# powerSupplyBoard_new.net
KiCad netlist of a schematic drawn in EAGLE
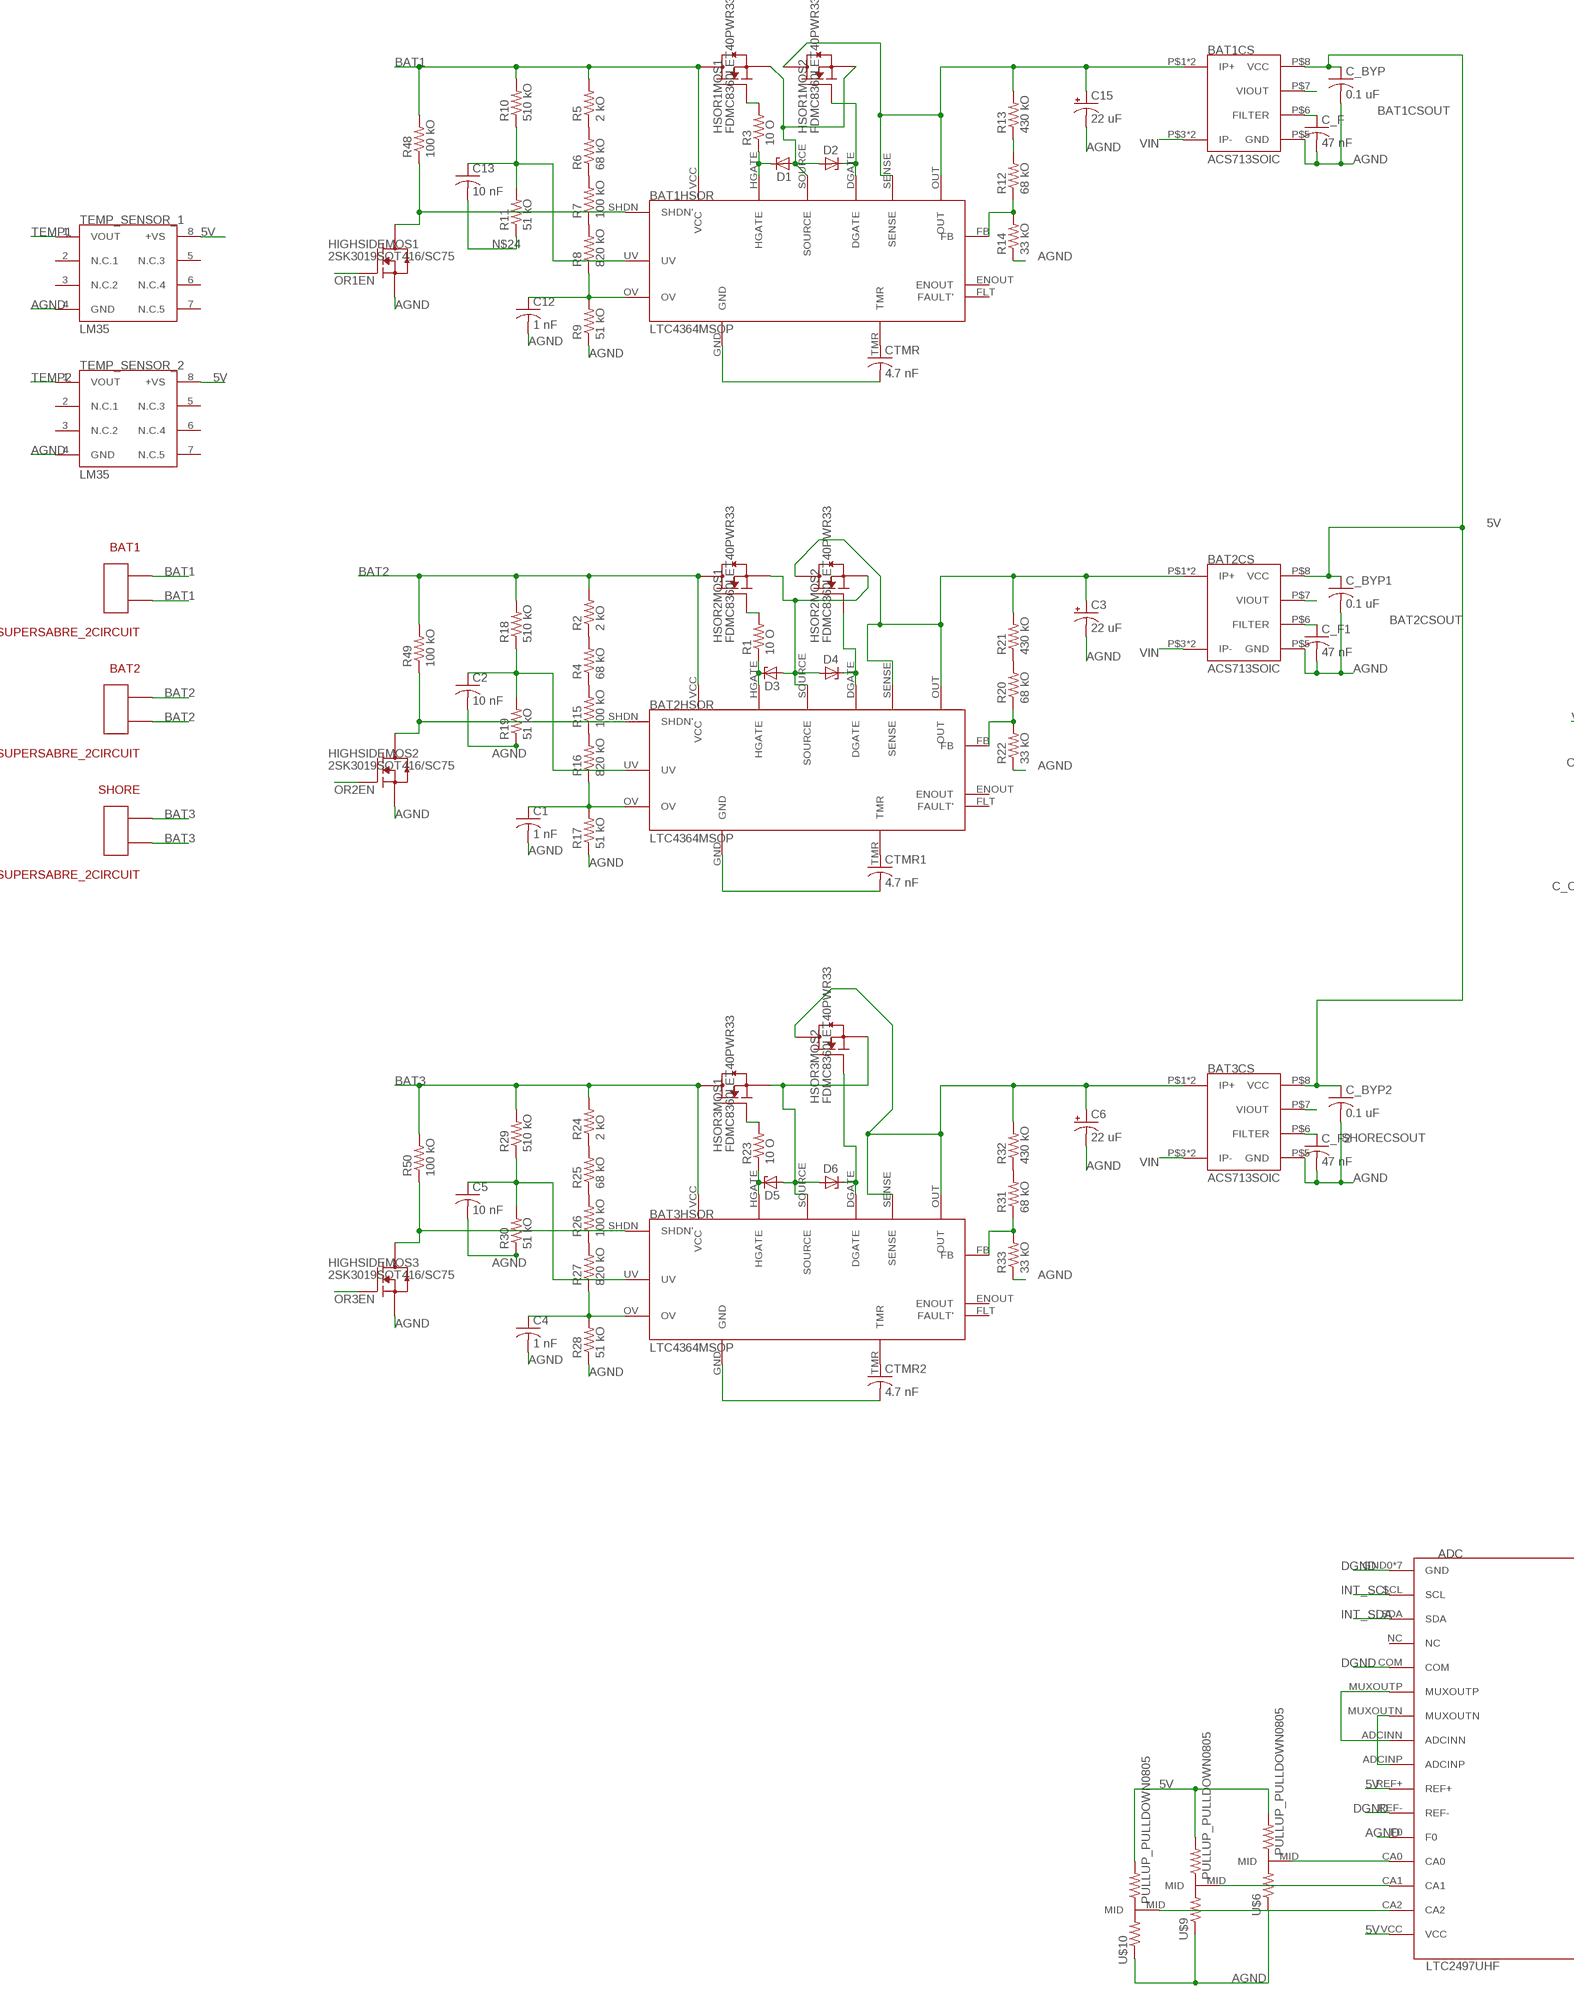
[diagram p0: schematic, sheet 1, part 1 of 2]
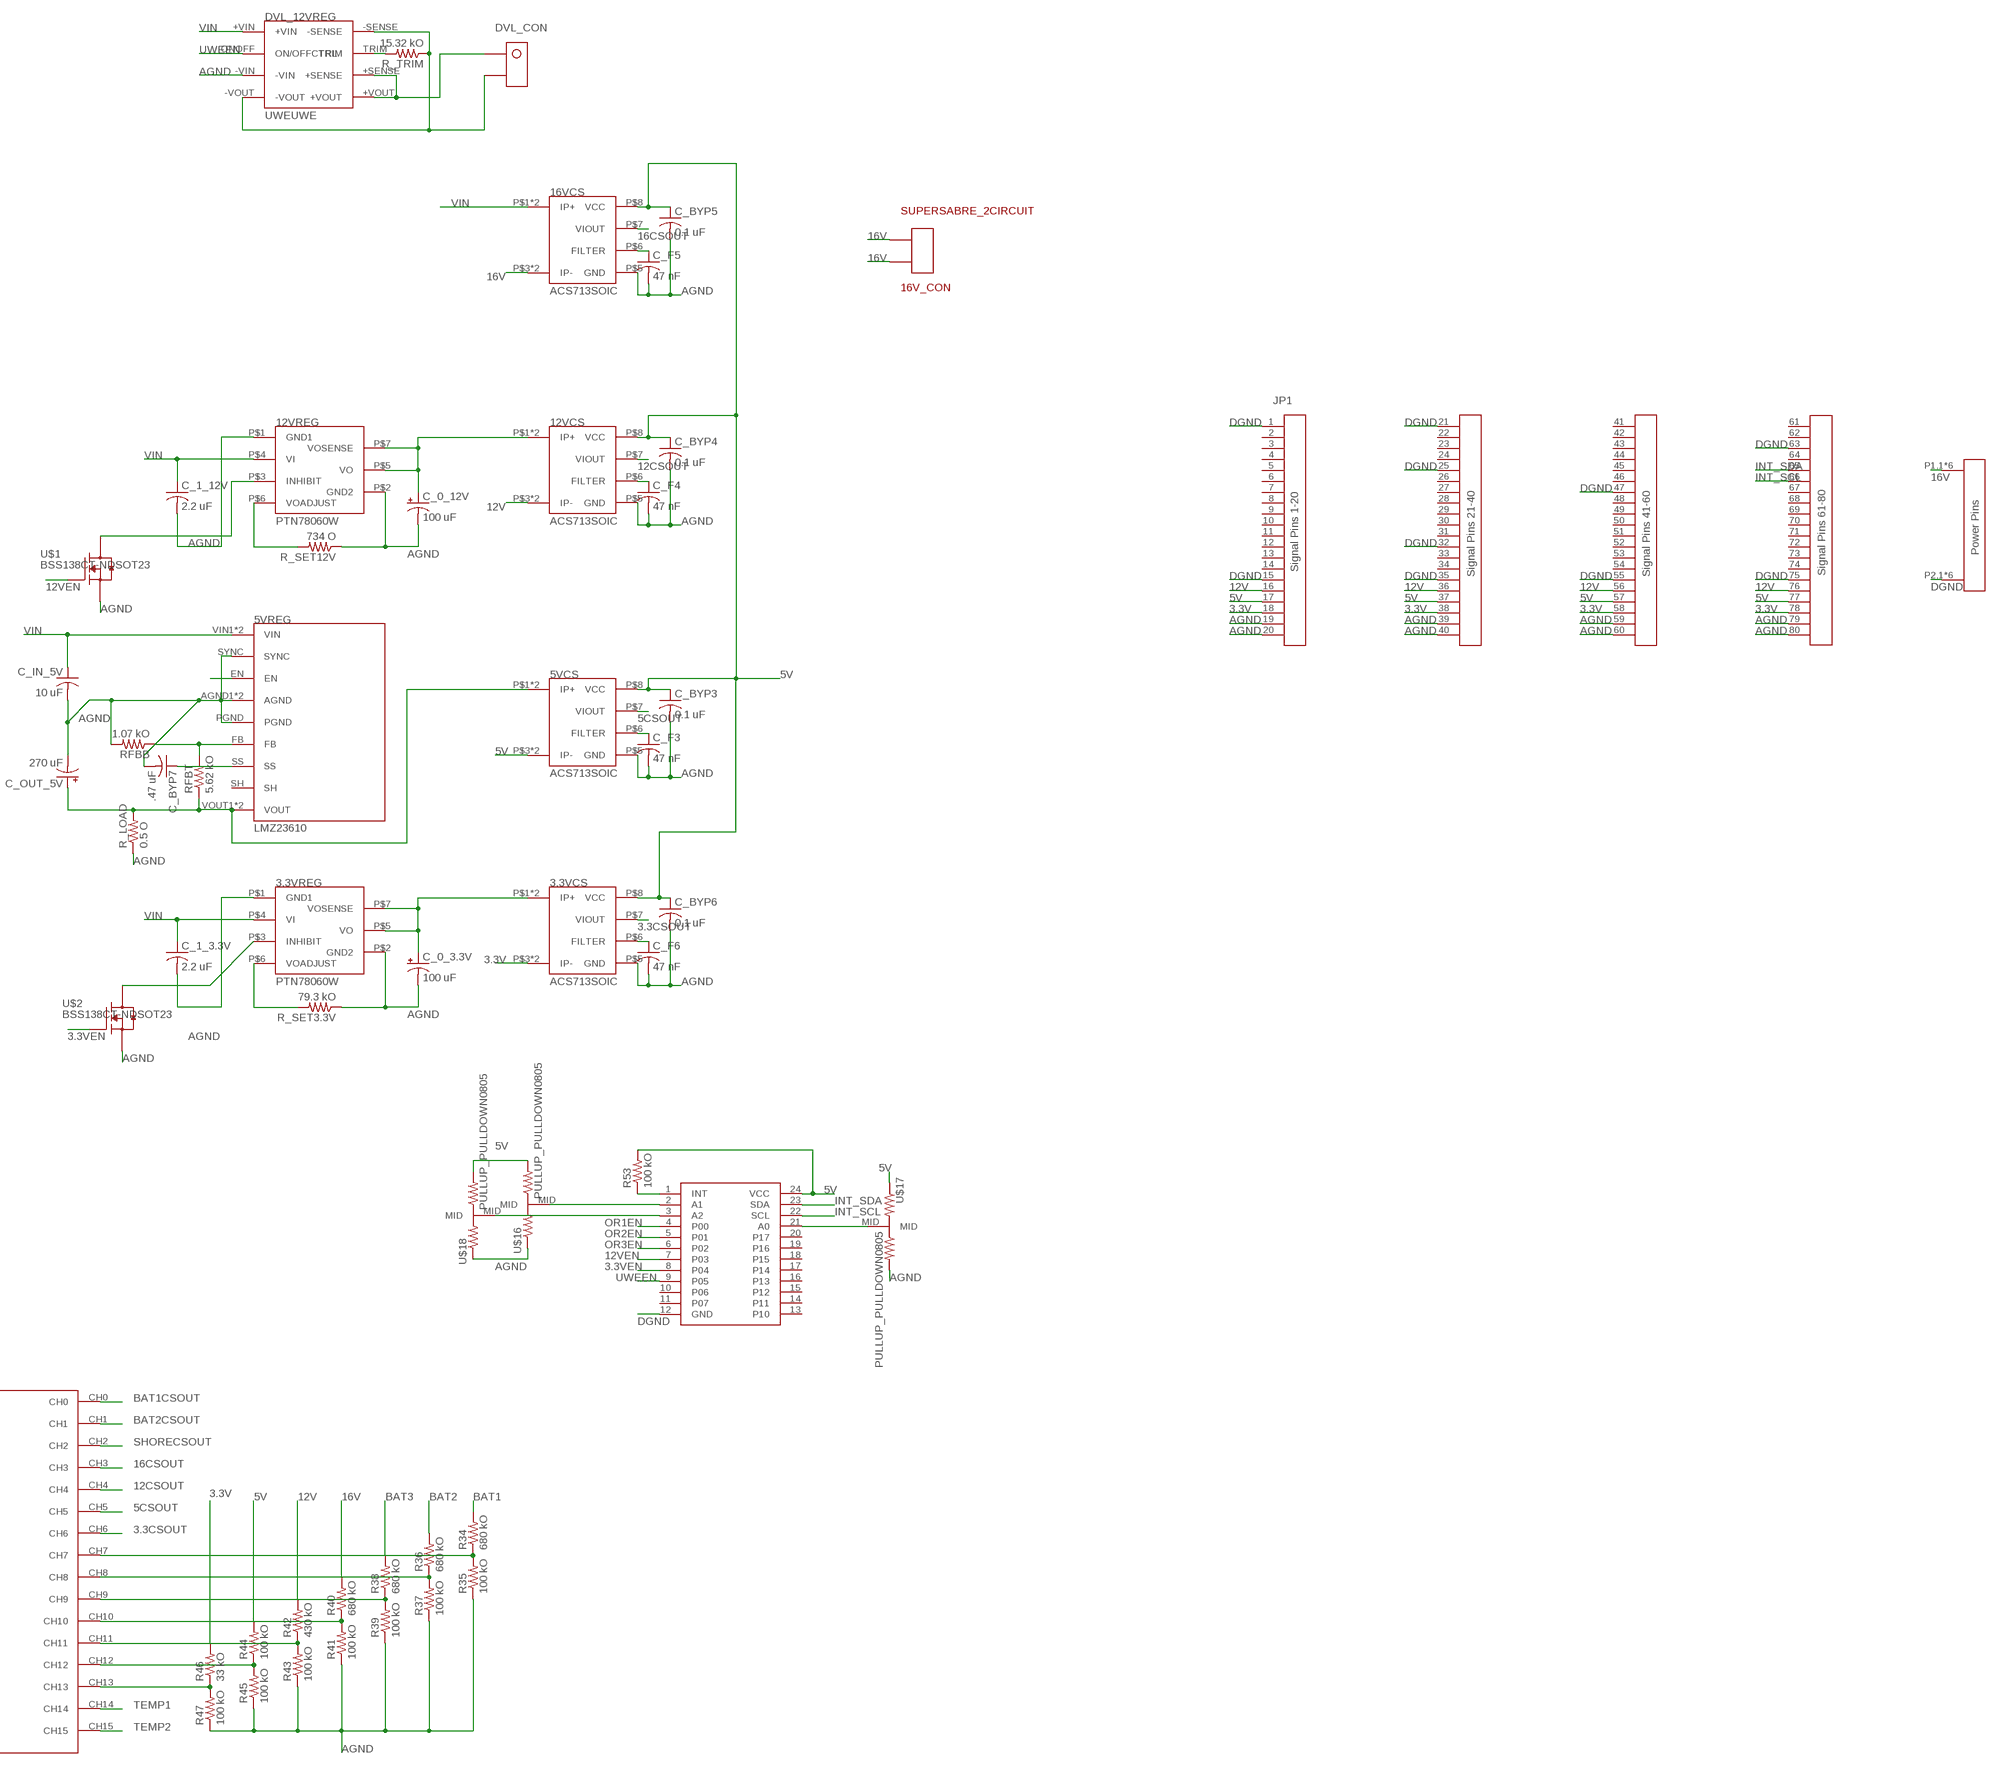
[diagram p1: schematic, sheet 1, part 2 of 2]

(export (version "E")
  (design (tool "Eeschema 10.0.6"))
  (components
    (comp (ref "3.3VCS")
      (value "ACS713SOIC")
      (footprint "eagle-import:ACS713-SOIC")
      (libsource (lib "eagle-import") (part "ACS713SOIC"))
    )
    (comp (ref "3.3VREG")
      (value "PTN78060W")
      (footprint "eagle-import:PTN78060W")
      (libsource (lib "eagle-import") (part "PTN78060W"))
    )
    (comp (ref "5VCS")
      (value "ACS713SOIC")
      (footprint "eagle-import:ACS713-SOIC")
      (libsource (lib "eagle-import") (part "ACS713SOIC"))
    )
    (comp (ref "5VREG")
      (value "LMZ23610")
      (footprint "eagle-import:LMZ23610")
      (libsource (lib "eagle-import") (part "LMZ23610"))
    )
    (comp (ref "12VCS")
      (value "ACS713SOIC")
      (footprint "eagle-import:ACS713-SOIC")
      (libsource (lib "eagle-import") (part "ACS713SOIC"))
    )
    (comp (ref "12VREG")
      (value "PTN78060W")
      (footprint "eagle-import:PTN78060W")
      (libsource (lib "eagle-import") (part "PTN78060W"))
    )
    (comp (ref "16VCS")
      (value "ACS713SOIC")
      (footprint "eagle-import:ACS713-SOIC")
      (libsource (lib "eagle-import") (part "ACS713SOIC"))
    )
    (comp (ref "16V_CON")
      (value "SUPERSABRE_2CIRCUIT")
      (footprint "eagle-import:SUPERSABRE_2CIRCUIT")
      (libsource (lib "eagle-import") (part "SUPERSABRE_2CIRCUIT"))
    )
    (comp (ref "ADC")
      (value "LTC2497UHF")
      (footprint "eagle-import:LTC2497-UHF")
      (libsource (lib "eagle-import") (part "LTC2497UHF"))
    )
    (comp (ref "BAT1")
      (value "SUPERSABRE_2CIRCUIT")
      (footprint "eagle-import:SUPERSABRE_2CIRCUIT")
      (libsource (lib "eagle-import") (part "SUPERSABRE_2CIRCUIT"))
    )
    (comp (ref "BAT1CS")
      (value "ACS713SOIC")
      (footprint "eagle-import:ACS713-SOIC")
      (libsource (lib "eagle-import") (part "ACS713SOIC"))
    )
    (comp (ref "BAT1HSOR")
      (value "LTC4364MSOP")
      (footprint "eagle-import:MSOP16")
      (libsource (lib "eagle-import") (part "LTC4364MSOP"))
    )
    (comp (ref "BAT2")
      (value "SUPERSABRE_2CIRCUIT")
      (footprint "eagle-import:SUPERSABRE_2CIRCUIT")
      (libsource (lib "eagle-import") (part "SUPERSABRE_2CIRCUIT"))
    )
    (comp (ref "BAT2CS")
      (value "ACS713SOIC")
      (footprint "eagle-import:ACS713-SOIC")
      (libsource (lib "eagle-import") (part "ACS713SOIC"))
    )
    (comp (ref "BAT2HSOR")
      (value "LTC4364MSOP")
      (footprint "eagle-import:MSOP16")
      (libsource (lib "eagle-import") (part "LTC4364MSOP"))
    )
    (comp (ref "BAT3CS")
      (value "ACS713SOIC")
      (footprint "eagle-import:ACS713-SOIC")
      (libsource (lib "eagle-import") (part "ACS713SOIC"))
    )
    (comp (ref "BAT3HSOR")
      (value "LTC4364MSOP")
      (footprint "eagle-import:MSOP16")
      (libsource (lib "eagle-import") (part "LTC4364MSOP"))
    )
    (comp (ref "C1")
      (value "1 nF")
      (footprint "eagle-import:C0805")
      (libsource (lib "eagle-import") (part "C-USC0805"))
    )
    (comp (ref "C2")
      (value "10 nF")
      (footprint "eagle-import:C0805")
      (libsource (lib "eagle-import") (part "C-USC0805"))
    )
    (comp (ref "C3")
      (value "22 uF")
      (footprint "eagle-import:PANASONIC_F")
      (libsource (lib "eagle-import") (part "CPOL-USF"))
    )
    (comp (ref "C4")
      (value "1 nF")
      (footprint "eagle-import:C0805")
      (libsource (lib "eagle-import") (part "C-USC0805"))
    )
    (comp (ref "C5")
      (value "10 nF")
      (footprint "eagle-import:C0805")
      (libsource (lib "eagle-import") (part "C-USC0805"))
    )
    (comp (ref "C6")
      (value "22 uF")
      (footprint "eagle-import:PANASONIC_F")
      (libsource (lib "eagle-import") (part "CPOL-USF"))
    )
    (comp (ref "C12")
      (value "1 nF")
      (footprint "eagle-import:C0805")
      (libsource (lib "eagle-import") (part "C-USC0805"))
    )
    (comp (ref "C13")
      (value "10 nF")
      (footprint "eagle-import:C0805")
      (libsource (lib "eagle-import") (part "C-USC0805"))
    )
    (comp (ref "C15")
      (value "22 uF")
      (footprint "eagle-import:PANASONIC_F")
      (libsource (lib "eagle-import") (part "CPOL-USF"))
    )
    (comp (ref "CTMR")
      (value "4.7 nF")
      (footprint "eagle-import:C0805")
      (libsource (lib "eagle-import") (part "C-USC0805"))
    )
    (comp (ref "CTMR1")
      (value "4.7 nF")
      (footprint "eagle-import:C0805")
      (libsource (lib "eagle-import") (part "C-USC0805"))
    )
    (comp (ref "CTMR2")
      (value "4.7 nF")
      (footprint "eagle-import:C0805")
      (libsource (lib "eagle-import") (part "C-USC0805"))
    )
    (comp (ref "C_0_3.3V")
      (value "100 uF")
      (footprint "eagle-import:PANASONIC_F")
      (libsource (lib "eagle-import") (part "CPOL-USF"))
    )
    (comp (ref "C_0_12V")
      (value "100 uF")
      (footprint "eagle-import:PANASONIC_F")
      (libsource (lib "eagle-import") (part "CPOL-USF"))
    )
    (comp (ref "C_1_3.3V")
      (value "2.2 uF")
      (footprint "eagle-import:C0805")
      (libsource (lib "eagle-import") (part "C-USC0805"))
    )
    (comp (ref "C_1_12V")
      (value "2.2 uF")
      (footprint "eagle-import:C0805")
      (libsource (lib "eagle-import") (part "C-USC0805"))
    )
    (comp (ref "C_BYP")
      (value "0.1 uF")
      (footprint "eagle-import:C0805")
      (libsource (lib "eagle-import") (part "C-USC0805"))
    )
    (comp (ref "C_BYP1")
      (value "0.1 uF")
      (footprint "eagle-import:C0805")
      (libsource (lib "eagle-import") (part "C-USC0805"))
    )
    (comp (ref "C_BYP2")
      (value "0.1 uF")
      (footprint "eagle-import:C0805")
      (libsource (lib "eagle-import") (part "C-USC0805"))
    )
    (comp (ref "C_BYP3")
      (value "0.1 uF")
      (footprint "eagle-import:C0805")
      (libsource (lib "eagle-import") (part "C-USC0805"))
    )
    (comp (ref "C_BYP4")
      (value "0.1 uF")
      (footprint "eagle-import:C0805")
      (libsource (lib "eagle-import") (part "C-USC0805"))
    )
    (comp (ref "C_BYP5")
      (value "0.1 uF")
      (footprint "eagle-import:C0805")
      (libsource (lib "eagle-import") (part "C-USC0805"))
    )
    (comp (ref "C_BYP6")
      (value "0.1 uF")
      (footprint "eagle-import:C0805")
      (libsource (lib "eagle-import") (part "C-USC0805"))
    )
    (comp (ref "C_BYP7")
      (value ".47 uF")
      (footprint "eagle-import:C0805")
      (libsource (lib "eagle-import") (part "C-USC0805"))
    )
    (comp (ref "C_F")
      (value "47 nF")
      (footprint "eagle-import:C0805")
      (libsource (lib "eagle-import") (part "C-USC0805"))
    )
    (comp (ref "C_F1")
      (value "47 nF")
      (footprint "eagle-import:C0805")
      (libsource (lib "eagle-import") (part "C-USC0805"))
    )
    (comp (ref "C_F2")
      (value "47 nF")
      (footprint "eagle-import:C0805")
      (libsource (lib "eagle-import") (part "C-USC0805"))
    )
    (comp (ref "C_F3")
      (value "47 nF")
      (footprint "eagle-import:C0805")
      (libsource (lib "eagle-import") (part "C-USC0805"))
    )
    (comp (ref "C_F4")
      (value "47 nF")
      (footprint "eagle-import:C0805")
      (libsource (lib "eagle-import") (part "C-USC0805"))
    )
    (comp (ref "C_F5")
      (value "47 nF")
      (footprint "eagle-import:C0805")
      (libsource (lib "eagle-import") (part "C-USC0805"))
    )
    (comp (ref "C_F6")
      (value "47 nF")
      (footprint "eagle-import:C0805")
      (libsource (lib "eagle-import") (part "C-USC0805"))
    )
    (comp (ref "C_IN_5V")
      (value "10 uF")
      (footprint "eagle-import:C0805")
      (libsource (lib "eagle-import") (part "C-USC0805"))
    )
    (comp (ref "C_OUT_5V")
      (value "270 uF")
      (footprint "eagle-import:PANASONIC_F")
      (libsource (lib "eagle-import") (part "CPOL-USF"))
    )
    (comp (ref "D1")
      (value "ZENER-DIODESOD323-W")
      (footprint "eagle-import:SOD323-W")
      (libsource (lib "eagle-import") (part "ZENER-DIODESOD323-W"))
    )
    (comp (ref "D2")
      (value "ZENER-DIODESOD323-W")
      (footprint "eagle-import:SOD323-W")
      (libsource (lib "eagle-import") (part "ZENER-DIODESOD323-W"))
    )
    (comp (ref "D3")
      (value "ZENER-DIODESOD323-W")
      (footprint "eagle-import:SOD323-W")
      (libsource (lib "eagle-import") (part "ZENER-DIODESOD323-W"))
    )
    (comp (ref "D4")
      (value "ZENER-DIODESOD323-W")
      (footprint "eagle-import:SOD323-W")
      (libsource (lib "eagle-import") (part "ZENER-DIODESOD323-W"))
    )
    (comp (ref "D5")
      (value "ZENER-DIODESOD323-W")
      (footprint "eagle-import:SOD323-W")
      (libsource (lib "eagle-import") (part "ZENER-DIODESOD323-W"))
    )
    (comp (ref "D6")
      (value "ZENER-DIODESOD323-W")
      (footprint "eagle-import:SOD323-W")
      (libsource (lib "eagle-import") (part "ZENER-DIODESOD323-W"))
    )
    (comp (ref "DVL_12VREG")
      (value "UWEUWE")
      (footprint "eagle-import:UWE")
      (libsource (lib "eagle-import") (part "UWEUWE"))
    )
    (comp (ref "DVL_CON")
      (value "KK254_VERT_2PIN22-29-2021")
      (footprint "eagle-import:KK254_VERT_2PIN")
      (libsource (lib "eagle-import") (part "KK254_VERT_2PIN22-29-2021"))
    )
    (comp (ref "HIGHSIDEMOS1")
      (value "2SK3019SOT416/SC75")
      (footprint "eagle-import:SOT416")
      (libsource (lib "eagle-import") (part "2SK3019SOT416/SC75"))
    )
    (comp (ref "HIGHSIDEMOS2")
      (value "2SK3019SOT416/SC75")
      (footprint "eagle-import:SOT416")
      (libsource (lib "eagle-import") (part "2SK3019SOT416/SC75"))
    )
    (comp (ref "HIGHSIDEMOS3")
      (value "2SK3019SOT416/SC75")
      (footprint "eagle-import:SOT416")
      (libsource (lib "eagle-import") (part "2SK3019SOT416/SC75"))
    )
    (comp (ref "HSOR1MOS1")
      (value "FDMC8360LET40PWR33")
      (footprint "eagle-import:POWER33")
      (libsource (lib "eagle-import") (part "FDMC8360LET40PWR33"))
    )
    (comp (ref "HSOR1MOS2")
      (value "FDMC8360LET40PWR33")
      (footprint "eagle-import:POWER33")
      (libsource (lib "eagle-import") (part "FDMC8360LET40PWR33"))
    )
    (comp (ref "HSOR2MOS1")
      (value "FDMC8360LET40PWR33")
      (footprint "eagle-import:POWER33")
      (libsource (lib "eagle-import") (part "FDMC8360LET40PWR33"))
    )
    (comp (ref "HSOR2MOS2")
      (value "FDMC8360LET40PWR33")
      (footprint "eagle-import:POWER33")
      (libsource (lib "eagle-import") (part "FDMC8360LET40PWR33"))
    )
    (comp (ref "HSOR3MOS1")
      (value "FDMC8360LET40PWR33")
      (footprint "eagle-import:POWER33")
      (libsource (lib "eagle-import") (part "FDMC8360LET40PWR33"))
    )
    (comp (ref "HSOR3MOS2")
      (value "FDMC8360LET40PWR33")
      (footprint "eagle-import:POWER33")
      (libsource (lib "eagle-import") (part "FDMC8360LET40PWR33"))
    )
    (comp (ref "IOEXPANDER")
      (value "PCF8575C")
      (footprint "eagle-import:PW_R-PDSO-G24")
      (libsource (lib "eagle-import") (part "PCF8575C"))
    )
    (comp (ref "JP1")
      (value "MPSC-01-80MPSC-RA-LC")
      (footprint "eagle-import:MPSC-01-80")
      (libsource (lib "eagle-import") (part "MPSC-01-80MPSC-RA-LC"))
    )
    (comp (ref "R1")
      (value "10 O")
      (footprint "eagle-import:R0805")
      (libsource (lib "eagle-import") (part "R-US_R0805"))
    )
    (comp (ref "R2")
      (value "2 kO")
      (footprint "eagle-import:R0805")
      (libsource (lib "eagle-import") (part "R-US_R0805"))
    )
    (comp (ref "R3")
      (value "10 O")
      (footprint "eagle-import:R0805")
      (libsource (lib "eagle-import") (part "R-US_R0805"))
    )
    (comp (ref "R4")
      (value "68 kO")
      (footprint "eagle-import:R0805")
      (libsource (lib "eagle-import") (part "R-US_R0805"))
    )
    (comp (ref "R5")
      (value "2 kO")
      (footprint "eagle-import:R0805")
      (libsource (lib "eagle-import") (part "R-US_R0805"))
    )
    (comp (ref "R6")
      (value "68 kO")
      (footprint "eagle-import:R0805")
      (libsource (lib "eagle-import") (part "R-US_R0805"))
    )
    (comp (ref "R7")
      (value "100 kO")
      (footprint "eagle-import:R0805")
      (libsource (lib "eagle-import") (part "R-US_R0805"))
    )
    (comp (ref "R8")
      (value "820 kO")
      (footprint "eagle-import:R0805")
      (libsource (lib "eagle-import") (part "R-US_R0805"))
    )
    (comp (ref "R9")
      (value "51 kO")
      (footprint "eagle-import:R0805")
      (libsource (lib "eagle-import") (part "R-US_R0805"))
    )
    (comp (ref "R10")
      (value "510 kO")
      (footprint "eagle-import:R0805")
      (libsource (lib "eagle-import") (part "R-US_R0805"))
    )
    (comp (ref "R11")
      (value "51 kO")
      (footprint "eagle-import:R0805")
      (libsource (lib "eagle-import") (part "R-US_R0805"))
    )
    (comp (ref "R12")
      (value "68 kO")
      (footprint "eagle-import:R0805")
      (libsource (lib "eagle-import") (part "R-US_R0805"))
    )
    (comp (ref "R13")
      (value "430 kO")
      (footprint "eagle-import:R0805")
      (libsource (lib "eagle-import") (part "R-US_R0805"))
    )
    (comp (ref "R14")
      (value "33 kO")
      (footprint "eagle-import:R0805")
      (libsource (lib "eagle-import") (part "R-US_R0805"))
    )
    (comp (ref "R15")
      (value "100 kO")
      (footprint "eagle-import:R0805")
      (libsource (lib "eagle-import") (part "R-US_R0805"))
    )
    (comp (ref "R16")
      (value "820 kO")
      (footprint "eagle-import:R0805")
      (libsource (lib "eagle-import") (part "R-US_R0805"))
    )
    (comp (ref "R17")
      (value "51 kO")
      (footprint "eagle-import:R0805")
      (libsource (lib "eagle-import") (part "R-US_R0805"))
    )
    (comp (ref "R18")
      (value "510 kO")
      (footprint "eagle-import:R0805")
      (libsource (lib "eagle-import") (part "R-US_R0805"))
    )
    (comp (ref "R19")
      (value "51 kO")
      (footprint "eagle-import:R0805")
      (libsource (lib "eagle-import") (part "R-US_R0805"))
    )
    (comp (ref "R20")
      (value "68 kO")
      (footprint "eagle-import:R0805")
      (libsource (lib "eagle-import") (part "R-US_R0805"))
    )
    (comp (ref "R21")
      (value "430 kO")
      (footprint "eagle-import:R0805")
      (libsource (lib "eagle-import") (part "R-US_R0805"))
    )
    (comp (ref "R22")
      (value "33 kO")
      (footprint "eagle-import:R0805")
      (libsource (lib "eagle-import") (part "R-US_R0805"))
    )
    (comp (ref "R23")
      (value "10 O")
      (footprint "eagle-import:R0805")
      (libsource (lib "eagle-import") (part "R-US_R0805"))
    )
    (comp (ref "R24")
      (value "2 kO")
      (footprint "eagle-import:R0805")
      (libsource (lib "eagle-import") (part "R-US_R0805"))
    )
    (comp (ref "R25")
      (value "68 kO")
      (footprint "eagle-import:R0805")
      (libsource (lib "eagle-import") (part "R-US_R0805"))
    )
    (comp (ref "R26")
      (value "100 kO")
      (footprint "eagle-import:R0805")
      (libsource (lib "eagle-import") (part "R-US_R0805"))
    )
    (comp (ref "R27")
      (value "820 kO")
      (footprint "eagle-import:R0805")
      (libsource (lib "eagle-import") (part "R-US_R0805"))
    )
    (comp (ref "R28")
      (value "51 kO")
      (footprint "eagle-import:R0805")
      (libsource (lib "eagle-import") (part "R-US_R0805"))
    )
    (comp (ref "R29")
      (value "510 kO")
      (footprint "eagle-import:R0805")
      (libsource (lib "eagle-import") (part "R-US_R0805"))
    )
    (comp (ref "R30")
      (value "51 kO")
      (footprint "eagle-import:R0805")
      (libsource (lib "eagle-import") (part "R-US_R0805"))
    )
    (comp (ref "R31")
      (value "68 kO")
      (footprint "eagle-import:R0805")
      (libsource (lib "eagle-import") (part "R-US_R0805"))
    )
    (comp (ref "R32")
      (value "430 kO")
      (footprint "eagle-import:R0805")
      (libsource (lib "eagle-import") (part "R-US_R0805"))
    )
    (comp (ref "R33")
      (value "33 kO")
      (footprint "eagle-import:R0805")
      (libsource (lib "eagle-import") (part "R-US_R0805"))
    )
    (comp (ref "R34")
      (value "680 kO")
      (footprint "eagle-import:R0805")
      (libsource (lib "eagle-import") (part "R-US_R0805"))
    )
    (comp (ref "R35")
      (value "100 kO")
      (footprint "eagle-import:R0805")
      (libsource (lib "eagle-import") (part "R-US_R0805"))
    )
    (comp (ref "R36")
      (value "680 kO")
      (footprint "eagle-import:R0805")
      (libsource (lib "eagle-import") (part "R-US_R0805"))
    )
    (comp (ref "R37")
      (value "100 kO")
      (footprint "eagle-import:R0805")
      (libsource (lib "eagle-import") (part "R-US_R0805"))
    )
    (comp (ref "R38")
      (value "680 kO")
      (footprint "eagle-import:R0805")
      (libsource (lib "eagle-import") (part "R-US_R0805"))
    )
    (comp (ref "R39")
      (value "100 kO")
      (footprint "eagle-import:R0805")
      (libsource (lib "eagle-import") (part "R-US_R0805"))
    )
    (comp (ref "R40")
      (value "680 kO")
      (footprint "eagle-import:R0805")
      (libsource (lib "eagle-import") (part "R-US_R0805"))
    )
    (comp (ref "R41")
      (value "100 kO")
      (footprint "eagle-import:R0805")
      (libsource (lib "eagle-import") (part "R-US_R0805"))
    )
    (comp (ref "R42")
      (value "430 kO")
      (footprint "eagle-import:R0805")
      (libsource (lib "eagle-import") (part "R-US_R0805"))
    )
    (comp (ref "R43")
      (value "100 kO")
      (footprint "eagle-import:R0805")
      (libsource (lib "eagle-import") (part "R-US_R0805"))
    )
    (comp (ref "R44")
      (value "100 kO")
      (footprint "eagle-import:R0805")
      (libsource (lib "eagle-import") (part "R-US_R0805"))
    )
    (comp (ref "R45")
      (value "100 kO")
      (footprint "eagle-import:R0805")
      (libsource (lib "eagle-import") (part "R-US_R0805"))
    )
    (comp (ref "R46")
      (value "33 kO")
      (footprint "eagle-import:R0805")
      (libsource (lib "eagle-import") (part "R-US_R0805"))
    )
    (comp (ref "R47")
      (value "100 kO")
      (footprint "eagle-import:R0805")
      (libsource (lib "eagle-import") (part "R-US_R0805"))
    )
    (comp (ref "R48")
      (value "100 kO")
      (footprint "eagle-import:R0805")
      (libsource (lib "eagle-import") (part "R-US_R0805"))
    )
    (comp (ref "R49")
      (value "100 kO")
      (footprint "eagle-import:R0805")
      (libsource (lib "eagle-import") (part "R-US_R0805"))
    )
    (comp (ref "R50")
      (value "100 kO")
      (footprint "eagle-import:R0805")
      (libsource (lib "eagle-import") (part "R-US_R0805"))
    )
    (comp (ref "R53")
      (value "100 kO")
      (footprint "eagle-import:R0805")
      (libsource (lib "eagle-import") (part "R-US_R0805"))
    )
    (comp (ref "RFBB")
      (value "1.07 kO")
      (footprint "eagle-import:R0805")
      (libsource (lib "eagle-import") (part "R-US_R0805"))
    )
    (comp (ref "RFBT")
      (value "5.62 kO")
      (footprint "eagle-import:R0805")
      (libsource (lib "eagle-import") (part "R-US_R0805"))
    )
    (comp (ref "R_LOAD")
      (value "0.5 O")
      (footprint "eagle-import:R0805")
      (libsource (lib "eagle-import") (part "R-US_R0805"))
    )
    (comp (ref "R_SET3.3V")
      (value "79.3 kO")
      (footprint "eagle-import:R0805")
      (libsource (lib "eagle-import") (part "R-US_R0805"))
    )
    (comp (ref "R_SET12V")
      (value "734 O")
      (footprint "eagle-import:R0805")
      (libsource (lib "eagle-import") (part "R-US_R0805"))
    )
    (comp (ref "R_TRIM")
      (value "15.32 kO")
      (footprint "eagle-import:R0805")
      (libsource (lib "eagle-import") (part "R-US_R0805"))
    )
    (comp (ref "SHORE")
      (value "SUPERSABRE_2CIRCUIT")
      (footprint "eagle-import:SUPERSABRE_2CIRCUIT")
      (libsource (lib "eagle-import") (part "SUPERSABRE_2CIRCUIT"))
    )
    (comp (ref "TEMP_SENSOR_1")
      (value "LM35")
      (footprint "eagle-import:LM35")
      (libsource (lib "eagle-import") (part "LM35"))
    )
    (comp (ref "TEMP_SENSOR_2")
      (value "LM35")
      (footprint "eagle-import:LM35")
      (libsource (lib "eagle-import") (part "LM35"))
    )
    (comp (ref "U$1")
      (value "BSS138CT-NDSOT23")
      (footprint "eagle-import:SOT23")
      (libsource (lib "eagle-import") (part "BSS138CT-NDSOT23"))
    )
    (comp (ref "U$2")
      (value "BSS138CT-NDSOT23")
      (footprint "eagle-import:SOT23")
      (libsource (lib "eagle-import") (part "BSS138CT-NDSOT23"))
    )
    (comp (ref "U$6")
      (value "PULLUP_PULLDOWN0805")
      (footprint "eagle-import:PULLUP_PULLDOWN_0805")
      (libsource (lib "eagle-import") (part "PULLUP_PULLDOWN0805"))
    )
    (comp (ref "U$9")
      (value "PULLUP_PULLDOWN0805")
      (footprint "eagle-import:PULLUP_PULLDOWN_0805")
      (libsource (lib "eagle-import") (part "PULLUP_PULLDOWN0805"))
    )
    (comp (ref "U$10")
      (value "PULLUP_PULLDOWN0805")
      (footprint "eagle-import:PULLUP_PULLDOWN_0805")
      (libsource (lib "eagle-import") (part "PULLUP_PULLDOWN0805"))
    )
    (comp (ref "U$16")
      (value "PULLUP_PULLDOWN0805")
      (footprint "eagle-import:PULLUP_PULLDOWN_0805")
      (libsource (lib "eagle-import") (part "PULLUP_PULLDOWN0805"))
    )
    (comp (ref "U$17")
      (value "PULLUP_PULLDOWN0805")
      (footprint "eagle-import:PULLUP_PULLDOWN_0805")
      (libsource (lib "eagle-import") (part "PULLUP_PULLDOWN0805"))
    )
    (comp (ref "U$18")
      (value "PULLUP_PULLDOWN0805")
      (footprint "eagle-import:PULLUP_PULLDOWN_0805")
      (libsource (lib "eagle-import") (part "PULLUP_PULLDOWN0805"))
    )
  )
  (nets
    (net (code "1") (name "/3.3CSOUT") (class "Default")
      (node (ref "3.3VCS") (pin "P$7") (pinfunction "VIOUT_P$7") (pintype "bidirectional"))
      (node (ref "ADC") (pin "CH6") (pinfunction "CH6_CH6") (pintype "bidirectional"))
    )
    (net (code "2") (name "/3.3V") (class "Default")
      (node (ref "3.3VCS") (pin "P$3") (pinfunction "IP-_P$3") (pintype "bidirectional"))
      (node (ref "3.3VCS") (pin "P$4") (pinfunction "IP-_P$4") (pintype "bidirectional"))
      (node (ref "JP1") (pin "18") (pinfunction "P$18_18") (pintype "bidirectional"))
      (node (ref "JP1") (pin "38") (pinfunction "P$38_38") (pintype "bidirectional"))
      (node (ref "JP1") (pin "58") (pinfunction "P$58_58") (pintype "bidirectional"))
      (node (ref "JP1") (pin "78") (pinfunction "P$78_78") (pintype "bidirectional"))
      (node (ref "R46") (pin "2") (pinfunction "2_2") (pintype "passive"))
    )
    (net (code "3") (name "/3.3VEN") (class "Default")
      (node (ref "IOEXPANDER") (pin "8") (pinfunction "P04_8") (pintype "bidirectional"))
      (node (ref "U$2") (pin "1") (pinfunction "G_1") (pintype "passive"))
    )
    (net (code "4") (name "/5CSOUT") (class "Default")
      (node (ref "5VCS") (pin "P$7") (pinfunction "VIOUT_P$7") (pintype "bidirectional"))
      (node (ref "ADC") (pin "CH5") (pinfunction "CH5_CH5") (pintype "bidirectional"))
    )
    (net (code "5") (name "/5V") (class "Default")
      (node (ref "12VCS") (pin "P$8") (pinfunction "VCC_P$8") (pintype "bidirectional"))
      (node (ref "16VCS") (pin "P$8") (pinfunction "VCC_P$8") (pintype "bidirectional"))
      (node (ref "3.3VCS") (pin "P$8") (pinfunction "VCC_P$8") (pintype "bidirectional"))
      (node (ref "5VCS") (pin "P$3") (pinfunction "IP-_P$3") (pintype "bidirectional"))
      (node (ref "5VCS") (pin "P$4") (pinfunction "IP-_P$4") (pintype "bidirectional"))
      (node (ref "5VCS") (pin "P$8") (pinfunction "VCC_P$8") (pintype "bidirectional"))
      (node (ref "ADC") (pin "REF+") (pinfunction "REF+_REF+") (pintype "bidirectional"))
      (node (ref "ADC") (pin "VCC") (pinfunction "VCC_VCC") (pintype "bidirectional"))
      (node (ref "BAT1CS") (pin "P$8") (pinfunction "VCC_P$8") (pintype "bidirectional"))
      (node (ref "BAT2CS") (pin "P$8") (pinfunction "VCC_P$8") (pintype "bidirectional"))
      (node (ref "BAT3CS") (pin "P$8") (pinfunction "VCC_P$8") (pintype "bidirectional"))
      (node (ref "C_BYP") (pin "1") (pinfunction "1_1") (pintype "passive"))
      (node (ref "C_BYP1") (pin "1") (pinfunction "1_1") (pintype "passive"))
      (node (ref "C_BYP2") (pin "1") (pinfunction "1_1") (pintype "passive"))
      (node (ref "C_BYP3") (pin "1") (pinfunction "1_1") (pintype "passive"))
      (node (ref "C_BYP4") (pin "1") (pinfunction "1_1") (pintype "passive"))
      (node (ref "C_BYP5") (pin "1") (pinfunction "1_1") (pintype "passive"))
      (node (ref "C_BYP6") (pin "1") (pinfunction "1_1") (pintype "passive"))
      (node (ref "IOEXPANDER") (pin "24") (pinfunction "VCC_24") (pintype "bidirectional"))
      (node (ref "JP1") (pin "17") (pinfunction "P$17_17") (pintype "bidirectional"))
      (node (ref "JP1") (pin "37") (pinfunction "P$37_37") (pintype "bidirectional"))
      (node (ref "JP1") (pin "57") (pinfunction "P$57_57") (pintype "bidirectional"))
      (node (ref "JP1") (pin "77") (pinfunction "P$77_77") (pintype "bidirectional"))
      (node (ref "R44") (pin "2") (pinfunction "2_2") (pintype "passive"))
      (node (ref "R53") (pin "2") (pinfunction "2_2") (pintype "passive"))
      (node (ref "TEMP_SENSOR_1") (pin "8") (pinfunction "+VS_8") (pintype "bidirectional"))
      (node (ref "TEMP_SENSOR_2") (pin "8") (pinfunction "+VS_8") (pintype "bidirectional"))
      (node (ref "U$10") (pin "VCC") (pinfunction "PWR_VCC") (pintype "passive"))
      (node (ref "U$16") (pin "VCC") (pinfunction "PWR_VCC") (pintype "passive"))
      (node (ref "U$17") (pin "GND") (pinfunction "GND_GND") (pintype "passive"))
      (node (ref "U$18") (pin "VCC") (pinfunction "PWR_VCC") (pintype "passive"))
      (node (ref "U$6") (pin "VCC") (pinfunction "PWR_VCC") (pintype "passive"))
      (node (ref "U$9") (pin "VCC") (pinfunction "PWR_VCC") (pintype "passive"))
    )
    (net (code "6") (name "/12CSOUT") (class "Default")
      (node (ref "12VCS") (pin "P$7") (pinfunction "VIOUT_P$7") (pintype "bidirectional"))
      (node (ref "ADC") (pin "CH4") (pinfunction "CH4_CH4") (pintype "bidirectional"))
    )
    (net (code "7") (name "/12V") (class "Default")
      (node (ref "12VCS") (pin "P$3") (pinfunction "IP-_P$3") (pintype "bidirectional"))
      (node (ref "12VCS") (pin "P$4") (pinfunction "IP-_P$4") (pintype "bidirectional"))
      (node (ref "JP1") (pin "16") (pinfunction "P$16_16") (pintype "bidirectional"))
      (node (ref "JP1") (pin "36") (pinfunction "P$36_36") (pintype "bidirectional"))
      (node (ref "JP1") (pin "56") (pinfunction "P$56_56") (pintype "bidirectional"))
      (node (ref "JP1") (pin "76") (pinfunction "P$76_76") (pintype "bidirectional"))
      (node (ref "R42") (pin "2") (pinfunction "2_2") (pintype "passive"))
    )
    (net (code "8") (name "/12VEN") (class "Default")
      (node (ref "IOEXPANDER") (pin "7") (pinfunction "P03_7") (pintype "bidirectional"))
      (node (ref "U$1") (pin "1") (pinfunction "G_1") (pintype "passive"))
    )
    (net (code "9") (name "/16CSOUT") (class "Default")
      (node (ref "16VCS") (pin "P$7") (pinfunction "VIOUT_P$7") (pintype "bidirectional"))
      (node (ref "ADC") (pin "CH3") (pinfunction "CH3_CH3") (pintype "bidirectional"))
    )
    (net (code "10") (name "/16V") (class "Default")
      (node (ref "16VCS") (pin "P$3") (pinfunction "IP-_P$3") (pintype "bidirectional"))
      (node (ref "16VCS") (pin "P$4") (pinfunction "IP-_P$4") (pintype "bidirectional"))
      (node (ref "16V_CON") (pin "P$1") (pinfunction "P$1_P$1") (pintype "bidirectional"))
      (node (ref "16V_CON") (pin "P$2") (pinfunction "P$2_P$2") (pintype "bidirectional"))
      (node (ref "JP1") (pin "P1,1") (pinfunction "POWER1_P1,1") (pintype "bidirectional"))
      (node (ref "JP1") (pin "P1,2") (pinfunction "POWER1_P1,2") (pintype "bidirectional"))
      (node (ref "JP1") (pin "P1,3") (pinfunction "POWER1_P1,3") (pintype "bidirectional"))
      (node (ref "JP1") (pin "P1,4") (pinfunction "POWER1_P1,4") (pintype "bidirectional"))
      (node (ref "JP1") (pin "P1,5") (pinfunction "POWER1_P1,5") (pintype "bidirectional"))
      (node (ref "JP1") (pin "P1,6") (pinfunction "POWER1_P1,6") (pintype "bidirectional"))
      (node (ref "R40") (pin "2") (pinfunction "2_2") (pintype "passive"))
    )
    (net (code "11") (name "/AGND") (class "Default")
      (node (ref "12VCS") (pin "P$5") (pinfunction "GND_P$5") (pintype "bidirectional"))
      (node (ref "12VREG") (pin "P$1") (pinfunction "GND1_P$1") (pintype "bidirectional"))
      (node (ref "12VREG") (pin "P$2") (pinfunction "GND2_P$2") (pintype "bidirectional"))
      (node (ref "16VCS") (pin "P$5") (pinfunction "GND_P$5") (pintype "bidirectional"))
      (node (ref "3.3VCS") (pin "P$5") (pinfunction "GND_P$5") (pintype "bidirectional"))
      (node (ref "3.3VREG") (pin "P$1") (pinfunction "GND1_P$1") (pintype "bidirectional"))
      (node (ref "3.3VREG") (pin "P$2") (pinfunction "GND2_P$2") (pintype "bidirectional"))
      (node (ref "5VCS") (pin "P$5") (pinfunction "GND_P$5") (pintype "bidirectional"))
      (node (ref "5VREG") (pin "AGND1") (pinfunction "AGND_AGND1") (pintype "bidirectional"))
      (node (ref "5VREG") (pin "AGND2") (pinfunction "AGND_AGND2") (pintype "bidirectional"))
      (node (ref "5VREG") (pin "PGND") (pinfunction "PGND_PGND") (pintype "bidirectional"))
      (node (ref "5VREG") (pin "SYNC") (pinfunction "SYNC_SYNC") (pintype "bidirectional"))
      (node (ref "ADC") (pin "F0") (pinfunction "F0_F0") (pintype "bidirectional"))
      (node (ref "BAT1CS") (pin "P$5") (pinfunction "GND_P$5") (pintype "bidirectional"))
      (node (ref "BAT1HSOR") (pin "GND") (pinfunction "GND_GND") (pintype "bidirectional"))
      (node (ref "BAT2CS") (pin "P$5") (pinfunction "GND_P$5") (pintype "bidirectional"))
      (node (ref "BAT2HSOR") (pin "GND") (pinfunction "GND_GND") (pintype "bidirectional"))
      (node (ref "BAT3CS") (pin "P$5") (pinfunction "GND_P$5") (pintype "bidirectional"))
      (node (ref "BAT3HSOR") (pin "GND") (pinfunction "GND_GND") (pintype "bidirectional"))
      (node (ref "C1") (pin "2") (pinfunction "2_2") (pintype "passive"))
      (node (ref "C12") (pin "2") (pinfunction "2_2") (pintype "passive"))
      (node (ref "C15") (pin "-") (pinfunction "-_-") (pintype "passive"))
      (node (ref "C2") (pin "2") (pinfunction "2_2") (pintype "passive"))
      (node (ref "C3") (pin "-") (pinfunction "-_-") (pintype "passive"))
      (node (ref "C4") (pin "2") (pinfunction "2_2") (pintype "passive"))
      (node (ref "C5") (pin "2") (pinfunction "2_2") (pintype "passive"))
      (node (ref "C6") (pin "-") (pinfunction "-_-") (pintype "passive"))
      (node (ref "CTMR") (pin "2") (pinfunction "2_2") (pintype "passive"))
      (node (ref "CTMR1") (pin "2") (pinfunction "2_2") (pintype "passive"))
      (node (ref "CTMR2") (pin "2") (pinfunction "2_2") (pintype "passive"))
      (node (ref "C_0_12V") (pin "-") (pinfunction "-_-") (pintype "passive"))
      (node (ref "C_0_3.3V") (pin "-") (pinfunction "-_-") (pintype "passive"))
      (node (ref "C_1_12V") (pin "2") (pinfunction "2_2") (pintype "passive"))
      (node (ref "C_1_3.3V") (pin "2") (pinfunction "2_2") (pintype "passive"))
      (node (ref "C_BYP") (pin "2") (pinfunction "2_2") (pintype "passive"))
      (node (ref "C_BYP1") (pin "2") (pinfunction "2_2") (pintype "passive"))
      (node (ref "C_BYP2") (pin "2") (pinfunction "2_2") (pintype "passive"))
      (node (ref "C_BYP3") (pin "2") (pinfunction "2_2") (pintype "passive"))
      (node (ref "C_BYP4") (pin "2") (pinfunction "2_2") (pintype "passive"))
      (node (ref "C_BYP5") (pin "2") (pinfunction "2_2") (pintype "passive"))
      (node (ref "C_BYP6") (pin "2") (pinfunction "2_2") (pintype "passive"))
      (node (ref "C_BYP7") (pin "2") (pinfunction "2_2") (pintype "passive"))
      (node (ref "C_F") (pin "2") (pinfunction "2_2") (pintype "passive"))
      (node (ref "C_F1") (pin "2") (pinfunction "2_2") (pintype "passive"))
      (node (ref "C_F2") (pin "2") (pinfunction "2_2") (pintype "passive"))
      (node (ref "C_F3") (pin "2") (pinfunction "2_2") (pintype "passive"))
      (node (ref "C_F4") (pin "2") (pinfunction "2_2") (pintype "passive"))
      (node (ref "C_F5") (pin "2") (pinfunction "2_2") (pintype "passive"))
      (node (ref "C_F6") (pin "2") (pinfunction "2_2") (pintype "passive"))
      (node (ref "C_IN_5V") (pin "2") (pinfunction "2_2") (pintype "passive"))
      (node (ref "C_OUT_5V") (pin "-") (pinfunction "-_-") (pintype "passive"))
      (node (ref "DVL_12VREG") (pin "-VIN") (pinfunction "-VIN_-VIN") (pintype "bidirectional"))
      (node (ref "HIGHSIDEMOS1") (pin "S") (pinfunction "S_S") (pintype "passive"))
      (node (ref "HIGHSIDEMOS2") (pin "S") (pinfunction "S_S") (pintype "passive"))
      (node (ref "HIGHSIDEMOS3") (pin "S") (pinfunction "S_S") (pintype "passive"))
      (node (ref "JP1") (pin "19") (pinfunction "P$19_19") (pintype "bidirectional"))
      (node (ref "JP1") (pin "20") (pinfunction "P$20_20") (pintype "bidirectional"))
      (node (ref "JP1") (pin "39") (pinfunction "P$39_39") (pintype "bidirectional"))
      (node (ref "JP1") (pin "40") (pinfunction "P$40_40") (pintype "bidirectional"))
      (node (ref "JP1") (pin "59") (pinfunction "P$59_59") (pintype "bidirectional"))
      (node (ref "JP1") (pin "60") (pinfunction "P$60_60") (pintype "bidirectional"))
      (node (ref "JP1") (pin "79") (pinfunction "P$79_79") (pintype "bidirectional"))
      (node (ref "JP1") (pin "80") (pinfunction "P$80_80") (pintype "bidirectional"))
      (node (ref "R14") (pin "1") (pinfunction "1_1") (pintype "passive"))
      (node (ref "R17") (pin "1") (pinfunction "1_1") (pintype "passive"))
      (node (ref "R19") (pin "1") (pinfunction "1_1") (pintype "passive"))
      (node (ref "R22") (pin "1") (pinfunction "1_1") (pintype "passive"))
      (node (ref "R28") (pin "1") (pinfunction "1_1") (pintype "passive"))
      (node (ref "R30") (pin "1") (pinfunction "1_1") (pintype "passive"))
      (node (ref "R33") (pin "1") (pinfunction "1_1") (pintype "passive"))
      (node (ref "R35") (pin "1") (pinfunction "1_1") (pintype "passive"))
      (node (ref "R37") (pin "1") (pinfunction "1_1") (pintype "passive"))
      (node (ref "R39") (pin "1") (pinfunction "1_1") (pintype "passive"))
      (node (ref "R41") (pin "1") (pinfunction "1_1") (pintype "passive"))
      (node (ref "R43") (pin "1") (pinfunction "1_1") (pintype "passive"))
      (node (ref "R45") (pin "1") (pinfunction "1_1") (pintype "passive"))
      (node (ref "R47") (pin "1") (pinfunction "1_1") (pintype "passive"))
      (node (ref "R9") (pin "1") (pinfunction "1_1") (pintype "passive"))
      (node (ref "RFBB") (pin "2") (pinfunction "2_2") (pintype "passive"))
      (node (ref "R_LOAD") (pin "1") (pinfunction "1_1") (pintype "passive"))
      (node (ref "R_SET12V") (pin "1") (pinfunction "1_1") (pintype "passive"))
      (node (ref "R_SET3.3V") (pin "1") (pinfunction "1_1") (pintype "passive"))
      (node (ref "TEMP_SENSOR_1") (pin "4") (pinfunction "GND_4") (pintype "bidirectional"))
      (node (ref "TEMP_SENSOR_2") (pin "4") (pinfunction "GND_4") (pintype "bidirectional"))
      (node (ref "U$1") (pin "2") (pinfunction "S_2") (pintype "passive"))
      (node (ref "U$10") (pin "GND") (pinfunction "GND_GND") (pintype "passive"))
      (node (ref "U$16") (pin "GND") (pinfunction "GND_GND") (pintype "passive"))
      (node (ref "U$17") (pin "VCC") (pinfunction "PWR_VCC") (pintype "passive"))
      (node (ref "U$18") (pin "GND") (pinfunction "GND_GND") (pintype "passive"))
      (node (ref "U$2") (pin "2") (pinfunction "S_2") (pintype "passive"))
      (node (ref "U$6") (pin "GND") (pinfunction "GND_GND") (pintype "passive"))
      (node (ref "U$9") (pin "GND") (pinfunction "GND_GND") (pintype "passive"))
    )
    (net (code "12") (name "/BAT1") (class "Default")
      (node (ref "BAT1") (pin "P$1") (pinfunction "P$1_P$1") (pintype "bidirectional"))
      (node (ref "BAT1") (pin "P$2") (pinfunction "P$2_P$2") (pintype "bidirectional"))
      (node (ref "BAT1HSOR") (pin "VCC") (pinfunction "VCC_VCC") (pintype "bidirectional"))
      (node (ref "HSOR1MOS1") (pin "DRAIN") (pinfunction "DRAIN_DRAIN") (pintype "bidirectional"))
      (node (ref "R10") (pin "2") (pinfunction "2_2") (pintype "passive"))
      (node (ref "R34") (pin "2") (pinfunction "2_2") (pintype "passive"))
      (node (ref "R48") (pin "2") (pinfunction "2_2") (pintype "passive"))
      (node (ref "R5") (pin "2") (pinfunction "2_2") (pintype "passive"))
    )
    (net (code "13") (name "/BAT1CSOUT") (class "Default")
      (node (ref "ADC") (pin "CH0") (pinfunction "CH0_CH0") (pintype "bidirectional"))
      (node (ref "BAT1CS") (pin "P$7") (pinfunction "VIOUT_P$7") (pintype "bidirectional"))
    )
    (net (code "14") (name "/BAT2") (class "Default")
      (node (ref "BAT2") (pin "P$1") (pinfunction "P$1_P$1") (pintype "bidirectional"))
      (node (ref "BAT2") (pin "P$2") (pinfunction "P$2_P$2") (pintype "bidirectional"))
      (node (ref "BAT2HSOR") (pin "VCC") (pinfunction "VCC_VCC") (pintype "bidirectional"))
      (node (ref "HSOR2MOS1") (pin "DRAIN") (pinfunction "DRAIN_DRAIN") (pintype "bidirectional"))
      (node (ref "R18") (pin "2") (pinfunction "2_2") (pintype "passive"))
      (node (ref "R2") (pin "2") (pinfunction "2_2") (pintype "passive"))
      (node (ref "R36") (pin "2") (pinfunction "2_2") (pintype "passive"))
      (node (ref "R49") (pin "2") (pinfunction "2_2") (pintype "passive"))
    )
    (net (code "15") (name "/BAT2CSOUT") (class "Default")
      (node (ref "ADC") (pin "CH1") (pinfunction "CH1_CH1") (pintype "bidirectional"))
      (node (ref "BAT2CS") (pin "P$7") (pinfunction "VIOUT_P$7") (pintype "bidirectional"))
    )
    (net (code "16") (name "/BAT3") (class "Default")
      (node (ref "BAT3HSOR") (pin "VCC") (pinfunction "VCC_VCC") (pintype "bidirectional"))
      (node (ref "HSOR3MOS1") (pin "DRAIN") (pinfunction "DRAIN_DRAIN") (pintype "bidirectional"))
      (node (ref "R24") (pin "2") (pinfunction "2_2") (pintype "passive"))
      (node (ref "R29") (pin "2") (pinfunction "2_2") (pintype "passive"))
      (node (ref "R38") (pin "2") (pinfunction "2_2") (pintype "passive"))
      (node (ref "R50") (pin "2") (pinfunction "2_2") (pintype "passive"))
      (node (ref "SHORE") (pin "P$1") (pinfunction "P$1_P$1") (pintype "bidirectional"))
      (node (ref "SHORE") (pin "P$2") (pinfunction "P$2_P$2") (pintype "bidirectional"))
    )
    (net (code "17") (name "/DGND") (class "Default")
      (node (ref "ADC") (pin "COM") (pinfunction "COM_COM") (pintype "bidirectional"))
      (node (ref "ADC") (pin "GND0") (pinfunction "GND_GND0") (pintype "bidirectional"))
      (node (ref "ADC") (pin "GND1") (pinfunction "GND_GND1") (pintype "bidirectional"))
      (node (ref "ADC") (pin "GND2") (pinfunction "GND_GND2") (pintype "bidirectional"))
      (node (ref "ADC") (pin "GND3") (pinfunction "GND_GND3") (pintype "bidirectional"))
      (node (ref "ADC") (pin "GND4") (pinfunction "GND_GND4") (pintype "bidirectional"))
      (node (ref "ADC") (pin "GND5") (pinfunction "GND_GND5") (pintype "bidirectional"))
      (node (ref "ADC") (pin "GND6") (pinfunction "GND_GND6") (pintype "bidirectional"))
      (node (ref "ADC") (pin "REF-") (pinfunction "REF-_REF-") (pintype "bidirectional"))
      (node (ref "IOEXPANDER") (pin "12") (pinfunction "GND_12") (pintype "bidirectional"))
      (node (ref "JP1") (pin "1") (pinfunction "P$1_1") (pintype "bidirectional"))
      (node (ref "JP1") (pin "15") (pinfunction "P$15_15") (pintype "bidirectional"))
      (node (ref "JP1") (pin "21") (pinfunction "P$21_21") (pintype "bidirectional"))
      (node (ref "JP1") (pin "25") (pinfunction "P$25_25") (pintype "bidirectional"))
      (node (ref "JP1") (pin "32") (pinfunction "P$32_32") (pintype "bidirectional"))
      (node (ref "JP1") (pin "35") (pinfunction "P$35_35") (pintype "bidirectional"))
      (node (ref "JP1") (pin "47") (pinfunction "P$47_47") (pintype "bidirectional"))
      (node (ref "JP1") (pin "55") (pinfunction "P$55_55") (pintype "bidirectional"))
      (node (ref "JP1") (pin "63") (pinfunction "P$63_63") (pintype "bidirectional"))
      (node (ref "JP1") (pin "75") (pinfunction "P$75_75") (pintype "bidirectional"))
      (node (ref "JP1") (pin "P2,1") (pinfunction "POWER2_P2,1") (pintype "bidirectional"))
      (node (ref "JP1") (pin "P2,2") (pinfunction "POWER2_P2,2") (pintype "bidirectional"))
      (node (ref "JP1") (pin "P2,3") (pinfunction "POWER2_P2,3") (pintype "bidirectional"))
      (node (ref "JP1") (pin "P2,4") (pinfunction "POWER2_P2,4") (pintype "bidirectional"))
      (node (ref "JP1") (pin "P2,5") (pinfunction "POWER2_P2,5") (pintype "bidirectional"))
      (node (ref "JP1") (pin "P2,6") (pinfunction "POWER2_P2,6") (pintype "bidirectional"))
    )
    (net (code "18") (name "/INT_SCL") (class "Default")
      (node (ref "ADC") (pin "SCL") (pinfunction "SCL_SCL") (pintype "bidirectional"))
      (node (ref "IOEXPANDER") (pin "22") (pinfunction "SCL_22") (pintype "bidirectional"))
      (node (ref "JP1") (pin "66") (pinfunction "P$66_66") (pintype "bidirectional"))
    )
    (net (code "19") (name "/INT_SDA") (class "Default")
      (node (ref "ADC") (pin "SDA") (pinfunction "SDA_SDA") (pintype "bidirectional"))
      (node (ref "IOEXPANDER") (pin "23") (pinfunction "SDA_23") (pintype "bidirectional"))
      (node (ref "JP1") (pin "65") (pinfunction "P$65_65") (pintype "bidirectional"))
    )
    (net (code "20") (name "/N$24") (class "Default")
      (node (ref "C13") (pin "2") (pinfunction "2_2") (pintype "passive"))
      (node (ref "R11") (pin "1") (pinfunction "1_1") (pintype "passive"))
    )
    (net (code "21") (name "/OR1EN") (class "Default")
      (node (ref "HIGHSIDEMOS1") (pin "G") (pinfunction "G_G") (pintype "passive"))
      (node (ref "IOEXPANDER") (pin "4") (pinfunction "P00_4") (pintype "bidirectional"))
    )
    (net (code "22") (name "/OR2EN") (class "Default")
      (node (ref "HIGHSIDEMOS2") (pin "G") (pinfunction "G_G") (pintype "passive"))
      (node (ref "IOEXPANDER") (pin "5") (pinfunction "P01_5") (pintype "bidirectional"))
    )
    (net (code "23") (name "/OR3EN") (class "Default")
      (node (ref "HIGHSIDEMOS3") (pin "G") (pinfunction "G_G") (pintype "passive"))
      (node (ref "IOEXPANDER") (pin "6") (pinfunction "P02_6") (pintype "bidirectional"))
    )
    (net (code "24") (name "/SHORECSOUT") (class "Default")
      (node (ref "ADC") (pin "CH2") (pinfunction "CH2_CH2") (pintype "bidirectional"))
      (node (ref "BAT3CS") (pin "P$7") (pinfunction "VIOUT_P$7") (pintype "bidirectional"))
    )
    (net (code "25") (name "/TEMP1") (class "Default")
      (node (ref "ADC") (pin "CH14") (pinfunction "CH14_CH14") (pintype "bidirectional"))
      (node (ref "TEMP_SENSOR_1") (pin "1") (pinfunction "VOUT_1") (pintype "bidirectional"))
    )
    (net (code "26") (name "/TEMP2") (class "Default")
      (node (ref "ADC") (pin "CH15") (pinfunction "CH15_CH15") (pintype "bidirectional"))
      (node (ref "TEMP_SENSOR_2") (pin "1") (pinfunction "VOUT_1") (pintype "bidirectional"))
    )
    (net (code "27") (name "/UWEEN") (class "Default")
      (node (ref "DVL_12VREG") (pin "ONOFF") (pinfunction "ON/OFFCTRL_ONOFF") (pintype "bidirectional"))
      (node (ref "IOEXPANDER") (pin "9") (pinfunction "P05_9") (pintype "bidirectional"))
    )
    (net (code "28") (name "/VIN") (class "Default")
      (node (ref "12VREG") (pin "P$4") (pinfunction "VI_P$4") (pintype "bidirectional"))
      (node (ref "16VCS") (pin "P$1") (pinfunction "IP+_P$1") (pintype "bidirectional"))
      (node (ref "16VCS") (pin "P$2") (pinfunction "IP+_P$2") (pintype "bidirectional"))
      (node (ref "3.3VREG") (pin "P$4") (pinfunction "VI_P$4") (pintype "bidirectional"))
      (node (ref "5VREG") (pin "VIN1") (pinfunction "VIN_VIN1") (pintype "bidirectional"))
      (node (ref "5VREG") (pin "VIN2") (pinfunction "VIN_VIN2") (pintype "bidirectional"))
      (node (ref "BAT1CS") (pin "P$3") (pinfunction "IP-_P$3") (pintype "bidirectional"))
      (node (ref "BAT1CS") (pin "P$4") (pinfunction "IP-_P$4") (pintype "bidirectional"))
      (node (ref "BAT2CS") (pin "P$3") (pinfunction "IP-_P$3") (pintype "bidirectional"))
      (node (ref "BAT2CS") (pin "P$4") (pinfunction "IP-_P$4") (pintype "bidirectional"))
      (node (ref "BAT3CS") (pin "P$3") (pinfunction "IP-_P$3") (pintype "bidirectional"))
      (node (ref "BAT3CS") (pin "P$4") (pinfunction "IP-_P$4") (pintype "bidirectional"))
      (node (ref "C_1_12V") (pin "1") (pinfunction "1_1") (pintype "passive"))
      (node (ref "C_1_3.3V") (pin "1") (pinfunction "1_1") (pintype "passive"))
      (node (ref "C_IN_5V") (pin "1") (pinfunction "1_1") (pintype "passive"))
      (node (ref "DVL_12VREG") (pin "+VIN") (pinfunction "+VIN_+VIN") (pintype "bidirectional"))
    )
    (net (code "29") (name "Net-(3.3VCS-FILTER)") (class "Default")
      (node (ref "3.3VCS") (pin "P$6") (pinfunction "FILTER_P$6") (pintype "bidirectional"))
      (node (ref "C_F6") (pin "1") (pinfunction "1_1") (pintype "passive"))
    )
    (net (code "30") (name "Net-(3.3VREG-INHIBIT)") (class "Default")
      (node (ref "3.3VREG") (pin "P$3") (pinfunction "INHIBIT_P$3") (pintype "bidirectional"))
      (node (ref "U$2") (pin "3") (pinfunction "D_3") (pintype "bidirectional"))
    )
    (net (code "31") (name "Net-(3.3VREG-VO)") (class "Default")
      (node (ref "3.3VCS") (pin "P$1") (pinfunction "IP+_P$1") (pintype "bidirectional"))
      (node (ref "3.3VCS") (pin "P$2") (pinfunction "IP+_P$2") (pintype "bidirectional"))
      (node (ref "3.3VREG") (pin "P$5") (pinfunction "VO_P$5") (pintype "bidirectional"))
      (node (ref "3.3VREG") (pin "P$7") (pinfunction "VOSENSE_P$7") (pintype "bidirectional"))
      (node (ref "C_0_3.3V") (pin "+") (pinfunction "+_+") (pintype "passive"))
    )
    (net (code "32") (name "Net-(3.3VREG-VOADJUST)") (class "Default")
      (node (ref "3.3VREG") (pin "P$6") (pinfunction "VOADJUST_P$6") (pintype "bidirectional"))
      (node (ref "R_SET3.3V") (pin "2") (pinfunction "2_2") (pintype "passive"))
    )
    (net (code "33") (name "Net-(5VCS-FILTER)") (class "Default")
      (node (ref "5VCS") (pin "P$6") (pinfunction "FILTER_P$6") (pintype "bidirectional"))
      (node (ref "C_F3") (pin "1") (pinfunction "1_1") (pintype "passive"))
    )
    (net (code "34") (name "Net-(5VCS-IP+-PadP$1)") (class "Default")
      (node (ref "5VCS") (pin "P$1") (pinfunction "IP+_P$1") (pintype "bidirectional"))
      (node (ref "5VCS") (pin "P$2") (pinfunction "IP+_P$2") (pintype "bidirectional"))
      (node (ref "5VREG") (pin "VOUT1") (pinfunction "VOUT_VOUT1") (pintype "bidirectional"))
      (node (ref "5VREG") (pin "VOUT2") (pinfunction "VOUT_VOUT2") (pintype "bidirectional"))
      (node (ref "C_OUT_5V") (pin "+") (pinfunction "+_+") (pintype "passive"))
      (node (ref "RFBT") (pin "1") (pinfunction "1_1") (pintype "passive"))
      (node (ref "R_LOAD") (pin "2") (pinfunction "2_2") (pintype "passive"))
    )
    (net (code "35") (name "Net-(5VREG-PadFB)") (class "Default")
      (node (ref "5VREG") (pin "FB") (pinfunction "FB_FB") (pintype "bidirectional"))
      (node (ref "RFBB") (pin "1") (pinfunction "1_1") (pintype "passive"))
      (node (ref "RFBT") (pin "2") (pinfunction "2_2") (pintype "passive"))
    )
    (net (code "36") (name "Net-(5VREG-PadSS)") (class "Default")
      (node (ref "5VREG") (pin "SS") (pinfunction "SS_SS") (pintype "bidirectional"))
      (node (ref "C_BYP7") (pin "1") (pinfunction "1_1") (pintype "passive"))
    )
    (net (code "37") (name "Net-(12VCS-FILTER)") (class "Default")
      (node (ref "12VCS") (pin "P$6") (pinfunction "FILTER_P$6") (pintype "bidirectional"))
      (node (ref "C_F4") (pin "1") (pinfunction "1_1") (pintype "passive"))
    )
    (net (code "38") (name "Net-(12VREG-INHIBIT)") (class "Default")
      (node (ref "12VREG") (pin "P$3") (pinfunction "INHIBIT_P$3") (pintype "bidirectional"))
      (node (ref "U$1") (pin "3") (pinfunction "D_3") (pintype "bidirectional"))
    )
    (net (code "39") (name "Net-(12VREG-VO)") (class "Default")
      (node (ref "12VCS") (pin "P$1") (pinfunction "IP+_P$1") (pintype "bidirectional"))
      (node (ref "12VCS") (pin "P$2") (pinfunction "IP+_P$2") (pintype "bidirectional"))
      (node (ref "12VREG") (pin "P$5") (pinfunction "VO_P$5") (pintype "bidirectional"))
      (node (ref "12VREG") (pin "P$7") (pinfunction "VOSENSE_P$7") (pintype "bidirectional"))
      (node (ref "C_0_12V") (pin "+") (pinfunction "+_+") (pintype "passive"))
    )
    (net (code "40") (name "Net-(12VREG-VOADJUST)") (class "Default")
      (node (ref "12VREG") (pin "P$6") (pinfunction "VOADJUST_P$6") (pintype "bidirectional"))
      (node (ref "R_SET12V") (pin "2") (pinfunction "2_2") (pintype "passive"))
    )
    (net (code "41") (name "Net-(16VCS-FILTER)") (class "Default")
      (node (ref "16VCS") (pin "P$6") (pinfunction "FILTER_P$6") (pintype "bidirectional"))
      (node (ref "C_F5") (pin "1") (pinfunction "1_1") (pintype "passive"))
    )
    (net (code "42") (name "Net-(ADC-PadADCINN)") (class "Default")
      (node (ref "ADC") (pin "ADCINN") (pinfunction "ADCINN_ADCINN") (pintype "bidirectional"))
      (node (ref "ADC") (pin "MUXOUTP") (pinfunction "MUXOUTP_MUXOUTP") (pintype "bidirectional"))
    )
    (net (code "43") (name "Net-(ADC-PadADCINP)") (class "Default")
      (node (ref "ADC") (pin "ADCINP") (pinfunction "ADCINP_ADCINP") (pintype "bidirectional"))
      (node (ref "ADC") (pin "MUXOUTN") (pinfunction "MUXOUTN_MUXOUTN") (pintype "bidirectional"))
    )
    (net (code "44") (name "Net-(ADC-PadCA0)") (class "Default")
      (node (ref "ADC") (pin "CA0") (pinfunction "CA0_CA0") (pintype "bidirectional"))
      (node (ref "U$6") (pin "MID") (pinfunction "MID_MID") (pintype "bidirectional"))
    )
    (net (code "45") (name "Net-(ADC-PadCA1)") (class "Default")
      (node (ref "ADC") (pin "CA1") (pinfunction "CA1_CA1") (pintype "bidirectional"))
      (node (ref "U$9") (pin "MID") (pinfunction "MID_MID") (pintype "bidirectional"))
    )
    (net (code "46") (name "Net-(ADC-PadCA2)") (class "Default")
      (node (ref "ADC") (pin "CA2") (pinfunction "CA2_CA2") (pintype "bidirectional"))
      (node (ref "U$10") (pin "MID") (pinfunction "MID_MID") (pintype "bidirectional"))
    )
    (net (code "47") (name "Net-(ADC-PadCH7)") (class "Default")
      (node (ref "ADC") (pin "CH7") (pinfunction "CH7_CH7") (pintype "bidirectional"))
      (node (ref "R34") (pin "1") (pinfunction "1_1") (pintype "passive"))
      (node (ref "R35") (pin "2") (pinfunction "2_2") (pintype "passive"))
    )
    (net (code "48") (name "Net-(ADC-PadCH8)") (class "Default")
      (node (ref "ADC") (pin "CH8") (pinfunction "CH8_CH8") (pintype "bidirectional"))
      (node (ref "R36") (pin "1") (pinfunction "1_1") (pintype "passive"))
      (node (ref "R37") (pin "2") (pinfunction "2_2") (pintype "passive"))
    )
    (net (code "49") (name "Net-(ADC-PadCH9)") (class "Default")
      (node (ref "ADC") (pin "CH9") (pinfunction "CH9_CH9") (pintype "bidirectional"))
      (node (ref "R38") (pin "1") (pinfunction "1_1") (pintype "passive"))
      (node (ref "R39") (pin "2") (pinfunction "2_2") (pintype "passive"))
    )
    (net (code "50") (name "Net-(ADC-PadCH10)") (class "Default")
      (node (ref "ADC") (pin "CH10") (pinfunction "CH10_CH10") (pintype "bidirectional"))
      (node (ref "R40") (pin "1") (pinfunction "1_1") (pintype "passive"))
      (node (ref "R41") (pin "2") (pinfunction "2_2") (pintype "passive"))
    )
    (net (code "51") (name "Net-(ADC-PadCH11)") (class "Default")
      (node (ref "ADC") (pin "CH11") (pinfunction "CH11_CH11") (pintype "bidirectional"))
      (node (ref "R42") (pin "1") (pinfunction "1_1") (pintype "passive"))
      (node (ref "R43") (pin "2") (pinfunction "2_2") (pintype "passive"))
    )
    (net (code "52") (name "Net-(ADC-PadCH12)") (class "Default")
      (node (ref "ADC") (pin "CH12") (pinfunction "CH12_CH12") (pintype "bidirectional"))
      (node (ref "R44") (pin "1") (pinfunction "1_1") (pintype "passive"))
      (node (ref "R45") (pin "2") (pinfunction "2_2") (pintype "passive"))
    )
    (net (code "53") (name "Net-(ADC-PadCH13)") (class "Default")
      (node (ref "ADC") (pin "CH13") (pinfunction "CH13_CH13") (pintype "bidirectional"))
      (node (ref "R46") (pin "1") (pinfunction "1_1") (pintype "passive"))
      (node (ref "R47") (pin "2") (pinfunction "2_2") (pintype "passive"))
    )
    (net (code "54") (name "Net-(BAT1CS-FILTER)") (class "Default")
      (node (ref "BAT1CS") (pin "P$6") (pinfunction "FILTER_P$6") (pintype "bidirectional"))
      (node (ref "C_F") (pin "1") (pinfunction "1_1") (pintype "passive"))
    )
    (net (code "55") (name "Net-(BAT1CS-IP+-PadP$1)") (class "Default")
      (node (ref "BAT1CS") (pin "P$1") (pinfunction "IP+_P$1") (pintype "bidirectional"))
      (node (ref "BAT1CS") (pin "P$2") (pinfunction "IP+_P$2") (pintype "bidirectional"))
      (node (ref "BAT1HSOR") (pin "OUT") (pinfunction "OUT_OUT") (pintype "bidirectional"))
      (node (ref "BAT1HSOR") (pin "SENSE") (pinfunction "SENSE_SENSE") (pintype "bidirectional"))
      (node (ref "C15") (pin "+") (pinfunction "+_+") (pintype "passive"))
      (node (ref "HSOR1MOS2") (pin "DRAIN") (pinfunction "DRAIN_DRAIN") (pintype "bidirectional"))
      (node (ref "R13") (pin "2") (pinfunction "2_2") (pintype "passive"))
    )
    (net (code "56") (name "Net-(BAT1HSOR-PadDGATE)") (class "Default")
      (node (ref "BAT1HSOR") (pin "DGATE") (pinfunction "DGATE_DGATE") (pintype "bidirectional"))
      (node (ref "D2") (pin "C") (pinfunction "C_C") (pintype "passive"))
      (node (ref "HSOR1MOS2") (pin "GATE") (pinfunction "GATE_GATE") (pintype "passive"))
    )
    (net (code "57") (name "Net-(BAT1HSOR-PadFB)") (class "Default")
      (node (ref "BAT1HSOR") (pin "FB") (pinfunction "FB_FB") (pintype "bidirectional"))
      (node (ref "R12") (pin "1") (pinfunction "1_1") (pintype "passive"))
      (node (ref "R14") (pin "2") (pinfunction "2_2") (pintype "passive"))
    )
    (net (code "58") (name "Net-(BAT1HSOR-PadHGATE)") (class "Default")
      (node (ref "BAT1HSOR") (pin "HGATE") (pinfunction "HGATE_HGATE") (pintype "bidirectional"))
      (node (ref "D1") (pin "C") (pinfunction "C_C") (pintype "passive"))
      (node (ref "R3") (pin "1") (pinfunction "1_1") (pintype "passive"))
    )
    (net (code "59") (name "Net-(BAT1HSOR-PadOV)") (class "Default")
      (node (ref "BAT1HSOR") (pin "OV") (pinfunction "OV_OV") (pintype "bidirectional"))
      (node (ref "C12") (pin "1") (pinfunction "1_1") (pintype "passive"))
      (node (ref "R8") (pin "1") (pinfunction "1_1") (pintype "passive"))
      (node (ref "R9") (pin "2") (pinfunction "2_2") (pintype "passive"))
    )
    (net (code "60") (name "Net-(BAT1HSOR-PadSOURCE)") (class "Default")
      (node (ref "BAT1HSOR") (pin "SOURCE") (pinfunction "SOURCE_SOURCE") (pintype "bidirectional"))
      (node (ref "D1") (pin "A") (pinfunction "A_A") (pintype "passive"))
      (node (ref "D2") (pin "A") (pinfunction "A_A") (pintype "passive"))
      (node (ref "HSOR1MOS1") (pin "SOURCE1") (pinfunction "SOURCE_SOURCE1") (pintype "passive"))
      (node (ref "HSOR1MOS1") (pin "SOURCE2") (pinfunction "SOURCE_SOURCE2") (pintype "passive"))
      (node (ref "HSOR1MOS1") (pin "SOURCE3") (pinfunction "SOURCE_SOURCE3") (pintype "passive"))
      (node (ref "HSOR1MOS2") (pin "SOURCE1") (pinfunction "SOURCE_SOURCE1") (pintype "passive"))
      (node (ref "HSOR1MOS2") (pin "SOURCE2") (pinfunction "SOURCE_SOURCE2") (pintype "passive"))
      (node (ref "HSOR1MOS2") (pin "SOURCE3") (pinfunction "SOURCE_SOURCE3") (pintype "passive"))
    )
    (net (code "61") (name "Net-(BAT1HSOR-PadTMR)") (class "Default")
      (node (ref "BAT1HSOR") (pin "TMR") (pinfunction "TMR_TMR") (pintype "bidirectional"))
      (node (ref "CTMR") (pin "1") (pinfunction "1_1") (pintype "passive"))
    )
    (net (code "62") (name "Net-(BAT1HSOR-PadUV)") (class "Default")
      (node (ref "BAT1HSOR") (pin "UV") (pinfunction "UV_UV") (pintype "bidirectional"))
      (node (ref "C13") (pin "1") (pinfunction "1_1") (pintype "passive"))
      (node (ref "R10") (pin "1") (pinfunction "1_1") (pintype "passive"))
      (node (ref "R11") (pin "2") (pinfunction "2_2") (pintype "passive"))
    )
    (net (code "63") (name "Net-(BAT1HSOR-SHDN')") (class "Default")
      (node (ref "BAT1HSOR") (pin "SHDN") (pinfunction "SHDN'_SHDN") (pintype "bidirectional"))
      (node (ref "HIGHSIDEMOS1") (pin "D") (pinfunction "D_D") (pintype "bidirectional"))
      (node (ref "R48") (pin "1") (pinfunction "1_1") (pintype "passive"))
    )
    (net (code "64") (name "Net-(BAT2CS-FILTER)") (class "Default")
      (node (ref "BAT2CS") (pin "P$6") (pinfunction "FILTER_P$6") (pintype "bidirectional"))
      (node (ref "C_F1") (pin "1") (pinfunction "1_1") (pintype "passive"))
    )
    (net (code "65") (name "Net-(BAT2CS-IP+-PadP$1)") (class "Default")
      (node (ref "BAT2CS") (pin "P$1") (pinfunction "IP+_P$1") (pintype "bidirectional"))
      (node (ref "BAT2CS") (pin "P$2") (pinfunction "IP+_P$2") (pintype "bidirectional"))
      (node (ref "BAT2HSOR") (pin "OUT") (pinfunction "OUT_OUT") (pintype "bidirectional"))
      (node (ref "BAT2HSOR") (pin "SENSE") (pinfunction "SENSE_SENSE") (pintype "bidirectional"))
      (node (ref "C3") (pin "+") (pinfunction "+_+") (pintype "passive"))
      (node (ref "HSOR2MOS2") (pin "DRAIN") (pinfunction "DRAIN_DRAIN") (pintype "bidirectional"))
      (node (ref "R21") (pin "2") (pinfunction "2_2") (pintype "passive"))
    )
    (net (code "66") (name "Net-(BAT2HSOR-PadDGATE)") (class "Default")
      (node (ref "BAT2HSOR") (pin "DGATE") (pinfunction "DGATE_DGATE") (pintype "bidirectional"))
      (node (ref "D4") (pin "C") (pinfunction "C_C") (pintype "passive"))
      (node (ref "HSOR2MOS2") (pin "GATE") (pinfunction "GATE_GATE") (pintype "passive"))
    )
    (net (code "67") (name "Net-(BAT2HSOR-PadFB)") (class "Default")
      (node (ref "BAT2HSOR") (pin "FB") (pinfunction "FB_FB") (pintype "bidirectional"))
      (node (ref "R20") (pin "1") (pinfunction "1_1") (pintype "passive"))
      (node (ref "R22") (pin "2") (pinfunction "2_2") (pintype "passive"))
    )
    (net (code "68") (name "Net-(BAT2HSOR-PadHGATE)") (class "Default")
      (node (ref "BAT2HSOR") (pin "HGATE") (pinfunction "HGATE_HGATE") (pintype "bidirectional"))
      (node (ref "D3") (pin "C") (pinfunction "C_C") (pintype "passive"))
      (node (ref "R1") (pin "1") (pinfunction "1_1") (pintype "passive"))
    )
    (net (code "69") (name "Net-(BAT2HSOR-PadOV)") (class "Default")
      (node (ref "BAT2HSOR") (pin "OV") (pinfunction "OV_OV") (pintype "bidirectional"))
      (node (ref "C1") (pin "1") (pinfunction "1_1") (pintype "passive"))
      (node (ref "R16") (pin "1") (pinfunction "1_1") (pintype "passive"))
      (node (ref "R17") (pin "2") (pinfunction "2_2") (pintype "passive"))
    )
    (net (code "70") (name "Net-(BAT2HSOR-PadSOURCE)") (class "Default")
      (node (ref "BAT2HSOR") (pin "SOURCE") (pinfunction "SOURCE_SOURCE") (pintype "bidirectional"))
      (node (ref "D3") (pin "A") (pinfunction "A_A") (pintype "passive"))
      (node (ref "D4") (pin "A") (pinfunction "A_A") (pintype "passive"))
      (node (ref "HSOR2MOS1") (pin "SOURCE1") (pinfunction "SOURCE_SOURCE1") (pintype "passive"))
      (node (ref "HSOR2MOS1") (pin "SOURCE2") (pinfunction "SOURCE_SOURCE2") (pintype "passive"))
      (node (ref "HSOR2MOS1") (pin "SOURCE3") (pinfunction "SOURCE_SOURCE3") (pintype "passive"))
      (node (ref "HSOR2MOS2") (pin "SOURCE1") (pinfunction "SOURCE_SOURCE1") (pintype "passive"))
      (node (ref "HSOR2MOS2") (pin "SOURCE2") (pinfunction "SOURCE_SOURCE2") (pintype "passive"))
      (node (ref "HSOR2MOS2") (pin "SOURCE3") (pinfunction "SOURCE_SOURCE3") (pintype "passive"))
    )
    (net (code "71") (name "Net-(BAT2HSOR-PadTMR)") (class "Default")
      (node (ref "BAT2HSOR") (pin "TMR") (pinfunction "TMR_TMR") (pintype "bidirectional"))
      (node (ref "CTMR1") (pin "1") (pinfunction "1_1") (pintype "passive"))
    )
    (net (code "72") (name "Net-(BAT2HSOR-PadUV)") (class "Default")
      (node (ref "BAT2HSOR") (pin "UV") (pinfunction "UV_UV") (pintype "bidirectional"))
      (node (ref "C2") (pin "1") (pinfunction "1_1") (pintype "passive"))
      (node (ref "R18") (pin "1") (pinfunction "1_1") (pintype "passive"))
      (node (ref "R19") (pin "2") (pinfunction "2_2") (pintype "passive"))
    )
    (net (code "73") (name "Net-(BAT2HSOR-SHDN')") (class "Default")
      (node (ref "BAT2HSOR") (pin "SHDN") (pinfunction "SHDN'_SHDN") (pintype "bidirectional"))
      (node (ref "HIGHSIDEMOS2") (pin "D") (pinfunction "D_D") (pintype "bidirectional"))
      (node (ref "R49") (pin "1") (pinfunction "1_1") (pintype "passive"))
    )
    (net (code "74") (name "Net-(BAT3CS-FILTER)") (class "Default")
      (node (ref "BAT3CS") (pin "P$6") (pinfunction "FILTER_P$6") (pintype "bidirectional"))
      (node (ref "C_F2") (pin "1") (pinfunction "1_1") (pintype "passive"))
    )
    (net (code "75") (name "Net-(BAT3CS-IP+-PadP$1)") (class "Default")
      (node (ref "BAT3CS") (pin "P$1") (pinfunction "IP+_P$1") (pintype "bidirectional"))
      (node (ref "BAT3CS") (pin "P$2") (pinfunction "IP+_P$2") (pintype "bidirectional"))
      (node (ref "BAT3HSOR") (pin "OUT") (pinfunction "OUT_OUT") (pintype "bidirectional"))
      (node (ref "BAT3HSOR") (pin "SENSE") (pinfunction "SENSE_SENSE") (pintype "bidirectional"))
      (node (ref "C6") (pin "+") (pinfunction "+_+") (pintype "passive"))
      (node (ref "HSOR3MOS2") (pin "DRAIN") (pinfunction "DRAIN_DRAIN") (pintype "bidirectional"))
      (node (ref "R32") (pin "2") (pinfunction "2_2") (pintype "passive"))
    )
    (net (code "76") (name "Net-(BAT3HSOR-PadDGATE)") (class "Default")
      (node (ref "BAT3HSOR") (pin "DGATE") (pinfunction "DGATE_DGATE") (pintype "bidirectional"))
      (node (ref "D6") (pin "C") (pinfunction "C_C") (pintype "passive"))
      (node (ref "HSOR3MOS2") (pin "GATE") (pinfunction "GATE_GATE") (pintype "passive"))
    )
    (net (code "77") (name "Net-(BAT3HSOR-PadFB)") (class "Default")
      (node (ref "BAT3HSOR") (pin "FB") (pinfunction "FB_FB") (pintype "bidirectional"))
      (node (ref "R31") (pin "1") (pinfunction "1_1") (pintype "passive"))
      (node (ref "R33") (pin "2") (pinfunction "2_2") (pintype "passive"))
    )
    (net (code "78") (name "Net-(BAT3HSOR-PadHGATE)") (class "Default")
      (node (ref "BAT3HSOR") (pin "HGATE") (pinfunction "HGATE_HGATE") (pintype "bidirectional"))
      (node (ref "D5") (pin "C") (pinfunction "C_C") (pintype "passive"))
      (node (ref "R23") (pin "1") (pinfunction "1_1") (pintype "passive"))
    )
    (net (code "79") (name "Net-(BAT3HSOR-PadOV)") (class "Default")
      (node (ref "BAT3HSOR") (pin "OV") (pinfunction "OV_OV") (pintype "bidirectional"))
      (node (ref "C4") (pin "1") (pinfunction "1_1") (pintype "passive"))
      (node (ref "R27") (pin "1") (pinfunction "1_1") (pintype "passive"))
      (node (ref "R28") (pin "2") (pinfunction "2_2") (pintype "passive"))
    )
    (net (code "80") (name "Net-(BAT3HSOR-PadSOURCE)") (class "Default")
      (node (ref "BAT3HSOR") (pin "SOURCE") (pinfunction "SOURCE_SOURCE") (pintype "bidirectional"))
      (node (ref "D5") (pin "A") (pinfunction "A_A") (pintype "passive"))
      (node (ref "D6") (pin "A") (pinfunction "A_A") (pintype "passive"))
      (node (ref "HSOR3MOS1") (pin "SOURCE1") (pinfunction "SOURCE_SOURCE1") (pintype "passive"))
      (node (ref "HSOR3MOS1") (pin "SOURCE2") (pinfunction "SOURCE_SOURCE2") (pintype "passive"))
      (node (ref "HSOR3MOS1") (pin "SOURCE3") (pinfunction "SOURCE_SOURCE3") (pintype "passive"))
      (node (ref "HSOR3MOS2") (pin "SOURCE1") (pinfunction "SOURCE_SOURCE1") (pintype "passive"))
      (node (ref "HSOR3MOS2") (pin "SOURCE2") (pinfunction "SOURCE_SOURCE2") (pintype "passive"))
      (node (ref "HSOR3MOS2") (pin "SOURCE3") (pinfunction "SOURCE_SOURCE3") (pintype "passive"))
    )
    (net (code "81") (name "Net-(BAT3HSOR-PadTMR)") (class "Default")
      (node (ref "BAT3HSOR") (pin "TMR") (pinfunction "TMR_TMR") (pintype "bidirectional"))
      (node (ref "CTMR2") (pin "1") (pinfunction "1_1") (pintype "passive"))
    )
    (net (code "82") (name "Net-(BAT3HSOR-PadUV)") (class "Default")
      (node (ref "BAT3HSOR") (pin "UV") (pinfunction "UV_UV") (pintype "bidirectional"))
      (node (ref "C5") (pin "1") (pinfunction "1_1") (pintype "passive"))
      (node (ref "R29") (pin "1") (pinfunction "1_1") (pintype "passive"))
      (node (ref "R30") (pin "2") (pinfunction "2_2") (pintype "passive"))
    )
    (net (code "83") (name "Net-(BAT3HSOR-SHDN')") (class "Default")
      (node (ref "BAT3HSOR") (pin "SHDN") (pinfunction "SHDN'_SHDN") (pintype "bidirectional"))
      (node (ref "HIGHSIDEMOS3") (pin "D") (pinfunction "D_D") (pintype "bidirectional"))
      (node (ref "R50") (pin "1") (pinfunction "1_1") (pintype "passive"))
    )
    (net (code "84") (name "Net-(DVL_12VREG-Pad+SENSE)") (class "Default")
      (node (ref "DVL_12VREG") (pin "+SENSE") (pinfunction "+SENSE_+SENSE") (pintype "bidirectional"))
      (node (ref "DVL_12VREG") (pin "+VOUT") (pinfunction "+VOUT_+VOUT") (pintype "bidirectional"))
      (node (ref "DVL_CON") (pin "P$1") (pinfunction "P$1_P$1") (pintype "bidirectional"))
    )
    (net (code "85") (name "Net-(DVL_12VREG-Pad-SENSE)") (class "Default")
      (node (ref "DVL_12VREG") (pin "-SENSE") (pinfunction "-SENSE_-SENSE") (pintype "bidirectional"))
      (node (ref "DVL_12VREG") (pin "-VOUT") (pinfunction "-VOUT_-VOUT") (pintype "bidirectional"))
      (node (ref "DVL_CON") (pin "P$2") (pinfunction "P$2_P$2") (pintype "bidirectional"))
      (node (ref "R_TRIM") (pin "1") (pinfunction "1_1") (pintype "passive"))
    )
    (net (code "86") (name "Net-(DVL_12VREG-PadTRIM)") (class "Default")
      (node (ref "DVL_12VREG") (pin "TRIM") (pinfunction "TRIM_TRIM") (pintype "bidirectional"))
      (node (ref "R_TRIM") (pin "2") (pinfunction "2_2") (pintype "passive"))
    )
    (net (code "87") (name "Net-(HSOR1MOS1-PadGATE)") (class "Default")
      (node (ref "HSOR1MOS1") (pin "GATE") (pinfunction "GATE_GATE") (pintype "passive"))
      (node (ref "R3") (pin "2") (pinfunction "2_2") (pintype "passive"))
    )
    (net (code "88") (name "Net-(HSOR2MOS1-PadGATE)") (class "Default")
      (node (ref "HSOR2MOS1") (pin "GATE") (pinfunction "GATE_GATE") (pintype "passive"))
      (node (ref "R1") (pin "2") (pinfunction "2_2") (pintype "passive"))
    )
    (net (code "89") (name "Net-(HSOR3MOS1-PadGATE)") (class "Default")
      (node (ref "HSOR3MOS1") (pin "GATE") (pinfunction "GATE_GATE") (pintype "passive"))
      (node (ref "R23") (pin "2") (pinfunction "2_2") (pintype "passive"))
    )
    (net (code "90") (name "Net-(IOEXPANDER-A0)") (class "Default")
      (node (ref "IOEXPANDER") (pin "21") (pinfunction "A0_21") (pintype "bidirectional"))
      (node (ref "U$17") (pin "MID") (pinfunction "MID_MID") (pintype "bidirectional"))
    )
    (net (code "91") (name "Net-(IOEXPANDER-A1)") (class "Default")
      (node (ref "IOEXPANDER") (pin "2") (pinfunction "A1_2") (pintype "bidirectional"))
      (node (ref "U$16") (pin "MID") (pinfunction "MID_MID") (pintype "bidirectional"))
    )
    (net (code "92") (name "Net-(IOEXPANDER-A2)") (class "Default")
      (node (ref "IOEXPANDER") (pin "3") (pinfunction "A2_3") (pintype "bidirectional"))
      (node (ref "U$18") (pin "MID") (pinfunction "MID_MID") (pintype "bidirectional"))
    )
    (net (code "93") (name "Net-(IOEXPANDER-INT)") (class "Default")
      (node (ref "IOEXPANDER") (pin "1") (pinfunction "INT_1") (pintype "bidirectional"))
      (node (ref "R53") (pin "1") (pinfunction "1_1") (pintype "passive"))
    )
    (net (code "94") (name "Net-(R2-Pad1)") (class "Default")
      (node (ref "R2") (pin "1") (pinfunction "1_1") (pintype "passive"))
      (node (ref "R4") (pin "2") (pinfunction "2_2") (pintype "passive"))
    )
    (net (code "95") (name "Net-(R5-Pad1)") (class "Default")
      (node (ref "R5") (pin "1") (pinfunction "1_1") (pintype "passive"))
      (node (ref "R6") (pin "2") (pinfunction "2_2") (pintype "passive"))
    )
    (net (code "96") (name "Net-(R6-Pad1)") (class "Default")
      (node (ref "R6") (pin "1") (pinfunction "1_1") (pintype "passive"))
      (node (ref "R7") (pin "2") (pinfunction "2_2") (pintype "passive"))
    )
    (net (code "97") (name "Net-(R7-Pad1)") (class "Default")
      (node (ref "R7") (pin "1") (pinfunction "1_1") (pintype "passive"))
      (node (ref "R8") (pin "2") (pinfunction "2_2") (pintype "passive"))
    )
    (net (code "98") (name "Net-(R12-Pad2)") (class "Default")
      (node (ref "R12") (pin "2") (pinfunction "2_2") (pintype "passive"))
      (node (ref "R13") (pin "1") (pinfunction "1_1") (pintype "passive"))
    )
    (net (code "99") (name "Net-(R15-Pad1)") (class "Default")
      (node (ref "R15") (pin "1") (pinfunction "1_1") (pintype "passive"))
      (node (ref "R16") (pin "2") (pinfunction "2_2") (pintype "passive"))
    )
    (net (code "100") (name "Net-(R15-Pad2)") (class "Default")
      (node (ref "R15") (pin "2") (pinfunction "2_2") (pintype "passive"))
      (node (ref "R4") (pin "1") (pinfunction "1_1") (pintype "passive"))
    )
    (net (code "101") (name "Net-(R20-Pad2)") (class "Default")
      (node (ref "R20") (pin "2") (pinfunction "2_2") (pintype "passive"))
      (node (ref "R21") (pin "1") (pinfunction "1_1") (pintype "passive"))
    )
    (net (code "102") (name "Net-(R24-Pad1)") (class "Default")
      (node (ref "R24") (pin "1") (pinfunction "1_1") (pintype "passive"))
      (node (ref "R25") (pin "2") (pinfunction "2_2") (pintype "passive"))
    )
    (net (code "103") (name "Net-(R25-Pad1)") (class "Default")
      (node (ref "R25") (pin "1") (pinfunction "1_1") (pintype "passive"))
      (node (ref "R26") (pin "2") (pinfunction "2_2") (pintype "passive"))
    )
    (net (code "104") (name "Net-(R26-Pad1)") (class "Default")
      (node (ref "R26") (pin "1") (pinfunction "1_1") (pintype "passive"))
      (node (ref "R27") (pin "2") (pinfunction "2_2") (pintype "passive"))
    )
    (net (code "105") (name "Net-(R31-Pad2)") (class "Default")
      (node (ref "R31") (pin "2") (pinfunction "2_2") (pintype "passive"))
      (node (ref "R32") (pin "1") (pinfunction "1_1") (pintype "passive"))
    )
    (net (code "106") (name "unconnected-(5VREG-PadEN)") (class "Default")
      (node (ref "5VREG") (pin "EN") (pinfunction "EN_EN") (pintype "bidirectional"))
    )
    (net (code "107") (name "unconnected-(5VREG-PadSH)") (class "Default")
      (node (ref "5VREG") (pin "SH") (pinfunction "SH_SH") (pintype "bidirectional"))
    )
    (net (code "108") (name "unconnected-(ADC-PadNC)") (class "Default")
      (node (ref "ADC") (pin "NC") (pinfunction "NC_NC") (pintype "bidirectional"))
    )
    (net (code "109") (name "unconnected-(BAT1HSOR-FAULT'-PadFLT)") (class "Default")
      (node (ref "BAT1HSOR") (pin "FLT") (pinfunction "FAULT'_FLT") (pintype "bidirectional"))
    )
    (net (code "110") (name "unconnected-(BAT1HSOR-PadENOUT)") (class "Default")
      (node (ref "BAT1HSOR") (pin "ENOUT") (pinfunction "ENOUT_ENOUT") (pintype "bidirectional"))
    )
    (net (code "111") (name "unconnected-(BAT2HSOR-FAULT'-PadFLT)") (class "Default")
      (node (ref "BAT2HSOR") (pin "FLT") (pinfunction "FAULT'_FLT") (pintype "bidirectional"))
    )
    (net (code "112") (name "unconnected-(BAT2HSOR-PadENOUT)") (class "Default")
      (node (ref "BAT2HSOR") (pin "ENOUT") (pinfunction "ENOUT_ENOUT") (pintype "bidirectional"))
    )
    (net (code "113") (name "unconnected-(BAT3HSOR-FAULT'-PadFLT)") (class "Default")
      (node (ref "BAT3HSOR") (pin "FLT") (pinfunction "FAULT'_FLT") (pintype "bidirectional"))
    )
    (net (code "114") (name "unconnected-(BAT3HSOR-PadENOUT)") (class "Default")
      (node (ref "BAT3HSOR") (pin "ENOUT") (pinfunction "ENOUT_ENOUT") (pintype "bidirectional"))
    )
    (net (code "115") (name "unconnected-(IOEXPANDER-P06-Pad10)") (class "Default")
      (node (ref "IOEXPANDER") (pin "10") (pinfunction "P06_10") (pintype "bidirectional"))
    )
    (net (code "116") (name "unconnected-(IOEXPANDER-P07-Pad11)") (class "Default")
      (node (ref "IOEXPANDER") (pin "11") (pinfunction "P07_11") (pintype "bidirectional"))
    )
    (net (code "117") (name "unconnected-(IOEXPANDER-P10-Pad13)") (class "Default")
      (node (ref "IOEXPANDER") (pin "13") (pinfunction "P10_13") (pintype "bidirectional"))
    )
    (net (code "118") (name "unconnected-(IOEXPANDER-P11-Pad14)") (class "Default")
      (node (ref "IOEXPANDER") (pin "14") (pinfunction "P11_14") (pintype "bidirectional"))
    )
    (net (code "119") (name "unconnected-(IOEXPANDER-P12-Pad15)") (class "Default")
      (node (ref "IOEXPANDER") (pin "15") (pinfunction "P12_15") (pintype "bidirectional"))
    )
    (net (code "120") (name "unconnected-(IOEXPANDER-P13-Pad16)") (class "Default")
      (node (ref "IOEXPANDER") (pin "16") (pinfunction "P13_16") (pintype "bidirectional"))
    )
    (net (code "121") (name "unconnected-(IOEXPANDER-P14-Pad17)") (class "Default")
      (node (ref "IOEXPANDER") (pin "17") (pinfunction "P14_17") (pintype "bidirectional"))
    )
    (net (code "122") (name "unconnected-(IOEXPANDER-P15-Pad18)") (class "Default")
      (node (ref "IOEXPANDER") (pin "18") (pinfunction "P15_18") (pintype "bidirectional"))
    )
    (net (code "123") (name "unconnected-(IOEXPANDER-P16-Pad19)") (class "Default")
      (node (ref "IOEXPANDER") (pin "19") (pinfunction "P16_19") (pintype "bidirectional"))
    )
    (net (code "124") (name "unconnected-(IOEXPANDER-P17-Pad20)") (class "Default")
      (node (ref "IOEXPANDER") (pin "20") (pinfunction "P17_20") (pintype "bidirectional"))
    )
    (net (code "125") (name "unconnected-(JP1-P$2-Pad2)") (class "Default")
      (node (ref "JP1") (pin "2") (pinfunction "P$2_2") (pintype "bidirectional"))
    )
    (net (code "126") (name "unconnected-(JP1-P$3-Pad3)") (class "Default")
      (node (ref "JP1") (pin "3") (pinfunction "P$3_3") (pintype "bidirectional"))
    )
    (net (code "127") (name "unconnected-(JP1-P$4-Pad4)") (class "Default")
      (node (ref "JP1") (pin "4") (pinfunction "P$4_4") (pintype "bidirectional"))
    )
    (net (code "128") (name "unconnected-(JP1-P$5-Pad5)") (class "Default")
      (node (ref "JP1") (pin "5") (pinfunction "P$5_5") (pintype "bidirectional"))
    )
    (net (code "129") (name "unconnected-(JP1-P$6-Pad6)") (class "Default")
      (node (ref "JP1") (pin "6") (pinfunction "P$6_6") (pintype "bidirectional"))
    )
    (net (code "130") (name "unconnected-(JP1-P$7-Pad7)") (class "Default")
      (node (ref "JP1") (pin "7") (pinfunction "P$7_7") (pintype "bidirectional"))
    )
    (net (code "131") (name "unconnected-(JP1-P$8-Pad8)") (class "Default")
      (node (ref "JP1") (pin "8") (pinfunction "P$8_8") (pintype "bidirectional"))
    )
    (net (code "132") (name "unconnected-(JP1-P$9-Pad9)") (class "Default")
      (node (ref "JP1") (pin "9") (pinfunction "P$9_9") (pintype "bidirectional"))
    )
    (net (code "133") (name "unconnected-(JP1-P$10-Pad10)") (class "Default")
      (node (ref "JP1") (pin "10") (pinfunction "P$10_10") (pintype "bidirectional"))
    )
    (net (code "134") (name "unconnected-(JP1-P$11-Pad11)") (class "Default")
      (node (ref "JP1") (pin "11") (pinfunction "P$11_11") (pintype "bidirectional"))
    )
    (net (code "135") (name "unconnected-(JP1-P$12-Pad12)") (class "Default")
      (node (ref "JP1") (pin "12") (pinfunction "P$12_12") (pintype "bidirectional"))
    )
    (net (code "136") (name "unconnected-(JP1-P$13-Pad13)") (class "Default")
      (node (ref "JP1") (pin "13") (pinfunction "P$13_13") (pintype "bidirectional"))
    )
    (net (code "137") (name "unconnected-(JP1-P$14-Pad14)") (class "Default")
      (node (ref "JP1") (pin "14") (pinfunction "P$14_14") (pintype "bidirectional"))
    )
    (net (code "138") (name "unconnected-(JP1-P$22-Pad22)") (class "Default")
      (node (ref "JP1") (pin "22") (pinfunction "P$22_22") (pintype "bidirectional"))
    )
    (net (code "139") (name "unconnected-(JP1-P$23-Pad23)") (class "Default")
      (node (ref "JP1") (pin "23") (pinfunction "P$23_23") (pintype "bidirectional"))
    )
    (net (code "140") (name "unconnected-(JP1-P$24-Pad24)") (class "Default")
      (node (ref "JP1") (pin "24") (pinfunction "P$24_24") (pintype "bidirectional"))
    )
    (net (code "141") (name "unconnected-(JP1-P$26-Pad26)") (class "Default")
      (node (ref "JP1") (pin "26") (pinfunction "P$26_26") (pintype "bidirectional"))
    )
    (net (code "142") (name "unconnected-(JP1-P$27-Pad27)") (class "Default")
      (node (ref "JP1") (pin "27") (pinfunction "P$27_27") (pintype "bidirectional"))
    )
    (net (code "143") (name "unconnected-(JP1-P$28-Pad28)") (class "Default")
      (node (ref "JP1") (pin "28") (pinfunction "P$28_28") (pintype "bidirectional"))
    )
    (net (code "144") (name "unconnected-(JP1-P$29-Pad29)") (class "Default")
      (node (ref "JP1") (pin "29") (pinfunction "P$29_29") (pintype "bidirectional"))
    )
    (net (code "145") (name "unconnected-(JP1-P$30-Pad30)") (class "Default")
      (node (ref "JP1") (pin "30") (pinfunction "P$30_30") (pintype "bidirectional"))
    )
    (net (code "146") (name "unconnected-(JP1-P$31-Pad31)") (class "Default")
      (node (ref "JP1") (pin "31") (pinfunction "P$31_31") (pintype "bidirectional"))
    )
    (net (code "147") (name "unconnected-(JP1-P$33-Pad33)") (class "Default")
      (node (ref "JP1") (pin "33") (pinfunction "P$33_33") (pintype "bidirectional"))
    )
    (net (code "148") (name "unconnected-(JP1-P$34-Pad34)") (class "Default")
      (node (ref "JP1") (pin "34") (pinfunction "P$34_34") (pintype "bidirectional"))
    )
    (net (code "149") (name "unconnected-(JP1-P$41-Pad41)") (class "Default")
      (node (ref "JP1") (pin "41") (pinfunction "P$41_41") (pintype "bidirectional"))
    )
    (net (code "150") (name "unconnected-(JP1-P$42-Pad42)") (class "Default")
      (node (ref "JP1") (pin "42") (pinfunction "P$42_42") (pintype "bidirectional"))
    )
    (net (code "151") (name "unconnected-(JP1-P$43-Pad43)") (class "Default")
      (node (ref "JP1") (pin "43") (pinfunction "P$43_43") (pintype "bidirectional"))
    )
    (net (code "152") (name "unconnected-(JP1-P$44-Pad44)") (class "Default")
      (node (ref "JP1") (pin "44") (pinfunction "P$44_44") (pintype "bidirectional"))
    )
    (net (code "153") (name "unconnected-(JP1-P$45-Pad45)") (class "Default")
      (node (ref "JP1") (pin "45") (pinfunction "P$45_45") (pintype "bidirectional"))
    )
    (net (code "154") (name "unconnected-(JP1-P$46-Pad46)") (class "Default")
      (node (ref "JP1") (pin "46") (pinfunction "P$46_46") (pintype "bidirectional"))
    )
    (net (code "155") (name "unconnected-(JP1-P$48-Pad48)") (class "Default")
      (node (ref "JP1") (pin "48") (pinfunction "P$48_48") (pintype "bidirectional"))
    )
    (net (code "156") (name "unconnected-(JP1-P$49-Pad49)") (class "Default")
      (node (ref "JP1") (pin "49") (pinfunction "P$49_49") (pintype "bidirectional"))
    )
    (net (code "157") (name "unconnected-(JP1-P$50-Pad50)") (class "Default")
      (node (ref "JP1") (pin "50") (pinfunction "P$50_50") (pintype "bidirectional"))
    )
    (net (code "158") (name "unconnected-(JP1-P$51-Pad51)") (class "Default")
      (node (ref "JP1") (pin "51") (pinfunction "P$51_51") (pintype "bidirectional"))
    )
    (net (code "159") (name "unconnected-(JP1-P$52-Pad52)") (class "Default")
      (node (ref "JP1") (pin "52") (pinfunction "P$52_52") (pintype "bidirectional"))
    )
    (net (code "160") (name "unconnected-(JP1-P$53-Pad53)") (class "Default")
      (node (ref "JP1") (pin "53") (pinfunction "P$53_53") (pintype "bidirectional"))
    )
    (net (code "161") (name "unconnected-(JP1-P$54-Pad54)") (class "Default")
      (node (ref "JP1") (pin "54") (pinfunction "P$54_54") (pintype "bidirectional"))
    )
    (net (code "162") (name "unconnected-(JP1-P$61-Pad61)") (class "Default")
      (node (ref "JP1") (pin "61") (pinfunction "P$61_61") (pintype "bidirectional"))
    )
    (net (code "163") (name "unconnected-(JP1-P$62-Pad62)") (class "Default")
      (node (ref "JP1") (pin "62") (pinfunction "P$62_62") (pintype "bidirectional"))
    )
    (net (code "164") (name "unconnected-(JP1-P$64-Pad64)") (class "Default")
      (node (ref "JP1") (pin "64") (pinfunction "P$64_64") (pintype "bidirectional"))
    )
    (net (code "165") (name "unconnected-(JP1-P$67-Pad67)") (class "Default")
      (node (ref "JP1") (pin "67") (pinfunction "P$67_67") (pintype "bidirectional"))
    )
    (net (code "166") (name "unconnected-(JP1-P$68-Pad68)") (class "Default")
      (node (ref "JP1") (pin "68") (pinfunction "P$68_68") (pintype "bidirectional"))
    )
    (net (code "167") (name "unconnected-(JP1-P$69-Pad69)") (class "Default")
      (node (ref "JP1") (pin "69") (pinfunction "P$69_69") (pintype "bidirectional"))
    )
    (net (code "168") (name "unconnected-(JP1-P$70-Pad70)") (class "Default")
      (node (ref "JP1") (pin "70") (pinfunction "P$70_70") (pintype "bidirectional"))
    )
    (net (code "169") (name "unconnected-(JP1-P$71-Pad71)") (class "Default")
      (node (ref "JP1") (pin "71") (pinfunction "P$71_71") (pintype "bidirectional"))
    )
    (net (code "170") (name "unconnected-(JP1-P$72-Pad72)") (class "Default")
      (node (ref "JP1") (pin "72") (pinfunction "P$72_72") (pintype "bidirectional"))
    )
    (net (code "171") (name "unconnected-(JP1-P$73-Pad73)") (class "Default")
      (node (ref "JP1") (pin "73") (pinfunction "P$73_73") (pintype "bidirectional"))
    )
    (net (code "172") (name "unconnected-(JP1-P$74-Pad74)") (class "Default")
      (node (ref "JP1") (pin "74") (pinfunction "P$74_74") (pintype "bidirectional"))
    )
    (net (code "173") (name "unconnected-(TEMP_SENSOR_1-N.C.1-Pad2)") (class "Default")
      (node (ref "TEMP_SENSOR_1") (pin "2") (pinfunction "N.C.1_2") (pintype "bidirectional"))
    )
    (net (code "174") (name "unconnected-(TEMP_SENSOR_1-N.C.2-Pad3)") (class "Default")
      (node (ref "TEMP_SENSOR_1") (pin "3") (pinfunction "N.C.2_3") (pintype "bidirectional"))
    )
    (net (code "175") (name "unconnected-(TEMP_SENSOR_1-N.C.3-Pad5)") (class "Default")
      (node (ref "TEMP_SENSOR_1") (pin "5") (pinfunction "N.C.3_5") (pintype "bidirectional"))
    )
    (net (code "176") (name "unconnected-(TEMP_SENSOR_1-N.C.4-Pad6)") (class "Default")
      (node (ref "TEMP_SENSOR_1") (pin "6") (pinfunction "N.C.4_6") (pintype "bidirectional"))
    )
    (net (code "177") (name "unconnected-(TEMP_SENSOR_1-N.C.5-Pad7)") (class "Default")
      (node (ref "TEMP_SENSOR_1") (pin "7") (pinfunction "N.C.5_7") (pintype "bidirectional"))
    )
    (net (code "178") (name "unconnected-(TEMP_SENSOR_2-N.C.1-Pad2)") (class "Default")
      (node (ref "TEMP_SENSOR_2") (pin "2") (pinfunction "N.C.1_2") (pintype "bidirectional"))
    )
    (net (code "179") (name "unconnected-(TEMP_SENSOR_2-N.C.2-Pad3)") (class "Default")
      (node (ref "TEMP_SENSOR_2") (pin "3") (pinfunction "N.C.2_3") (pintype "bidirectional"))
    )
    (net (code "180") (name "unconnected-(TEMP_SENSOR_2-N.C.3-Pad5)") (class "Default")
      (node (ref "TEMP_SENSOR_2") (pin "5") (pinfunction "N.C.3_5") (pintype "bidirectional"))
    )
    (net (code "181") (name "unconnected-(TEMP_SENSOR_2-N.C.4-Pad6)") (class "Default")
      (node (ref "TEMP_SENSOR_2") (pin "6") (pinfunction "N.C.4_6") (pintype "bidirectional"))
    )
    (net (code "182") (name "unconnected-(TEMP_SENSOR_2-N.C.5-Pad7)") (class "Default")
      (node (ref "TEMP_SENSOR_2") (pin "7") (pinfunction "N.C.5_7") (pintype "bidirectional"))
    )
  )
)
